# SCH_Solenoid_Door_Lock_using_EM-18_2023-.net
KiCad netlist of a schematic drawn in EasyEDA
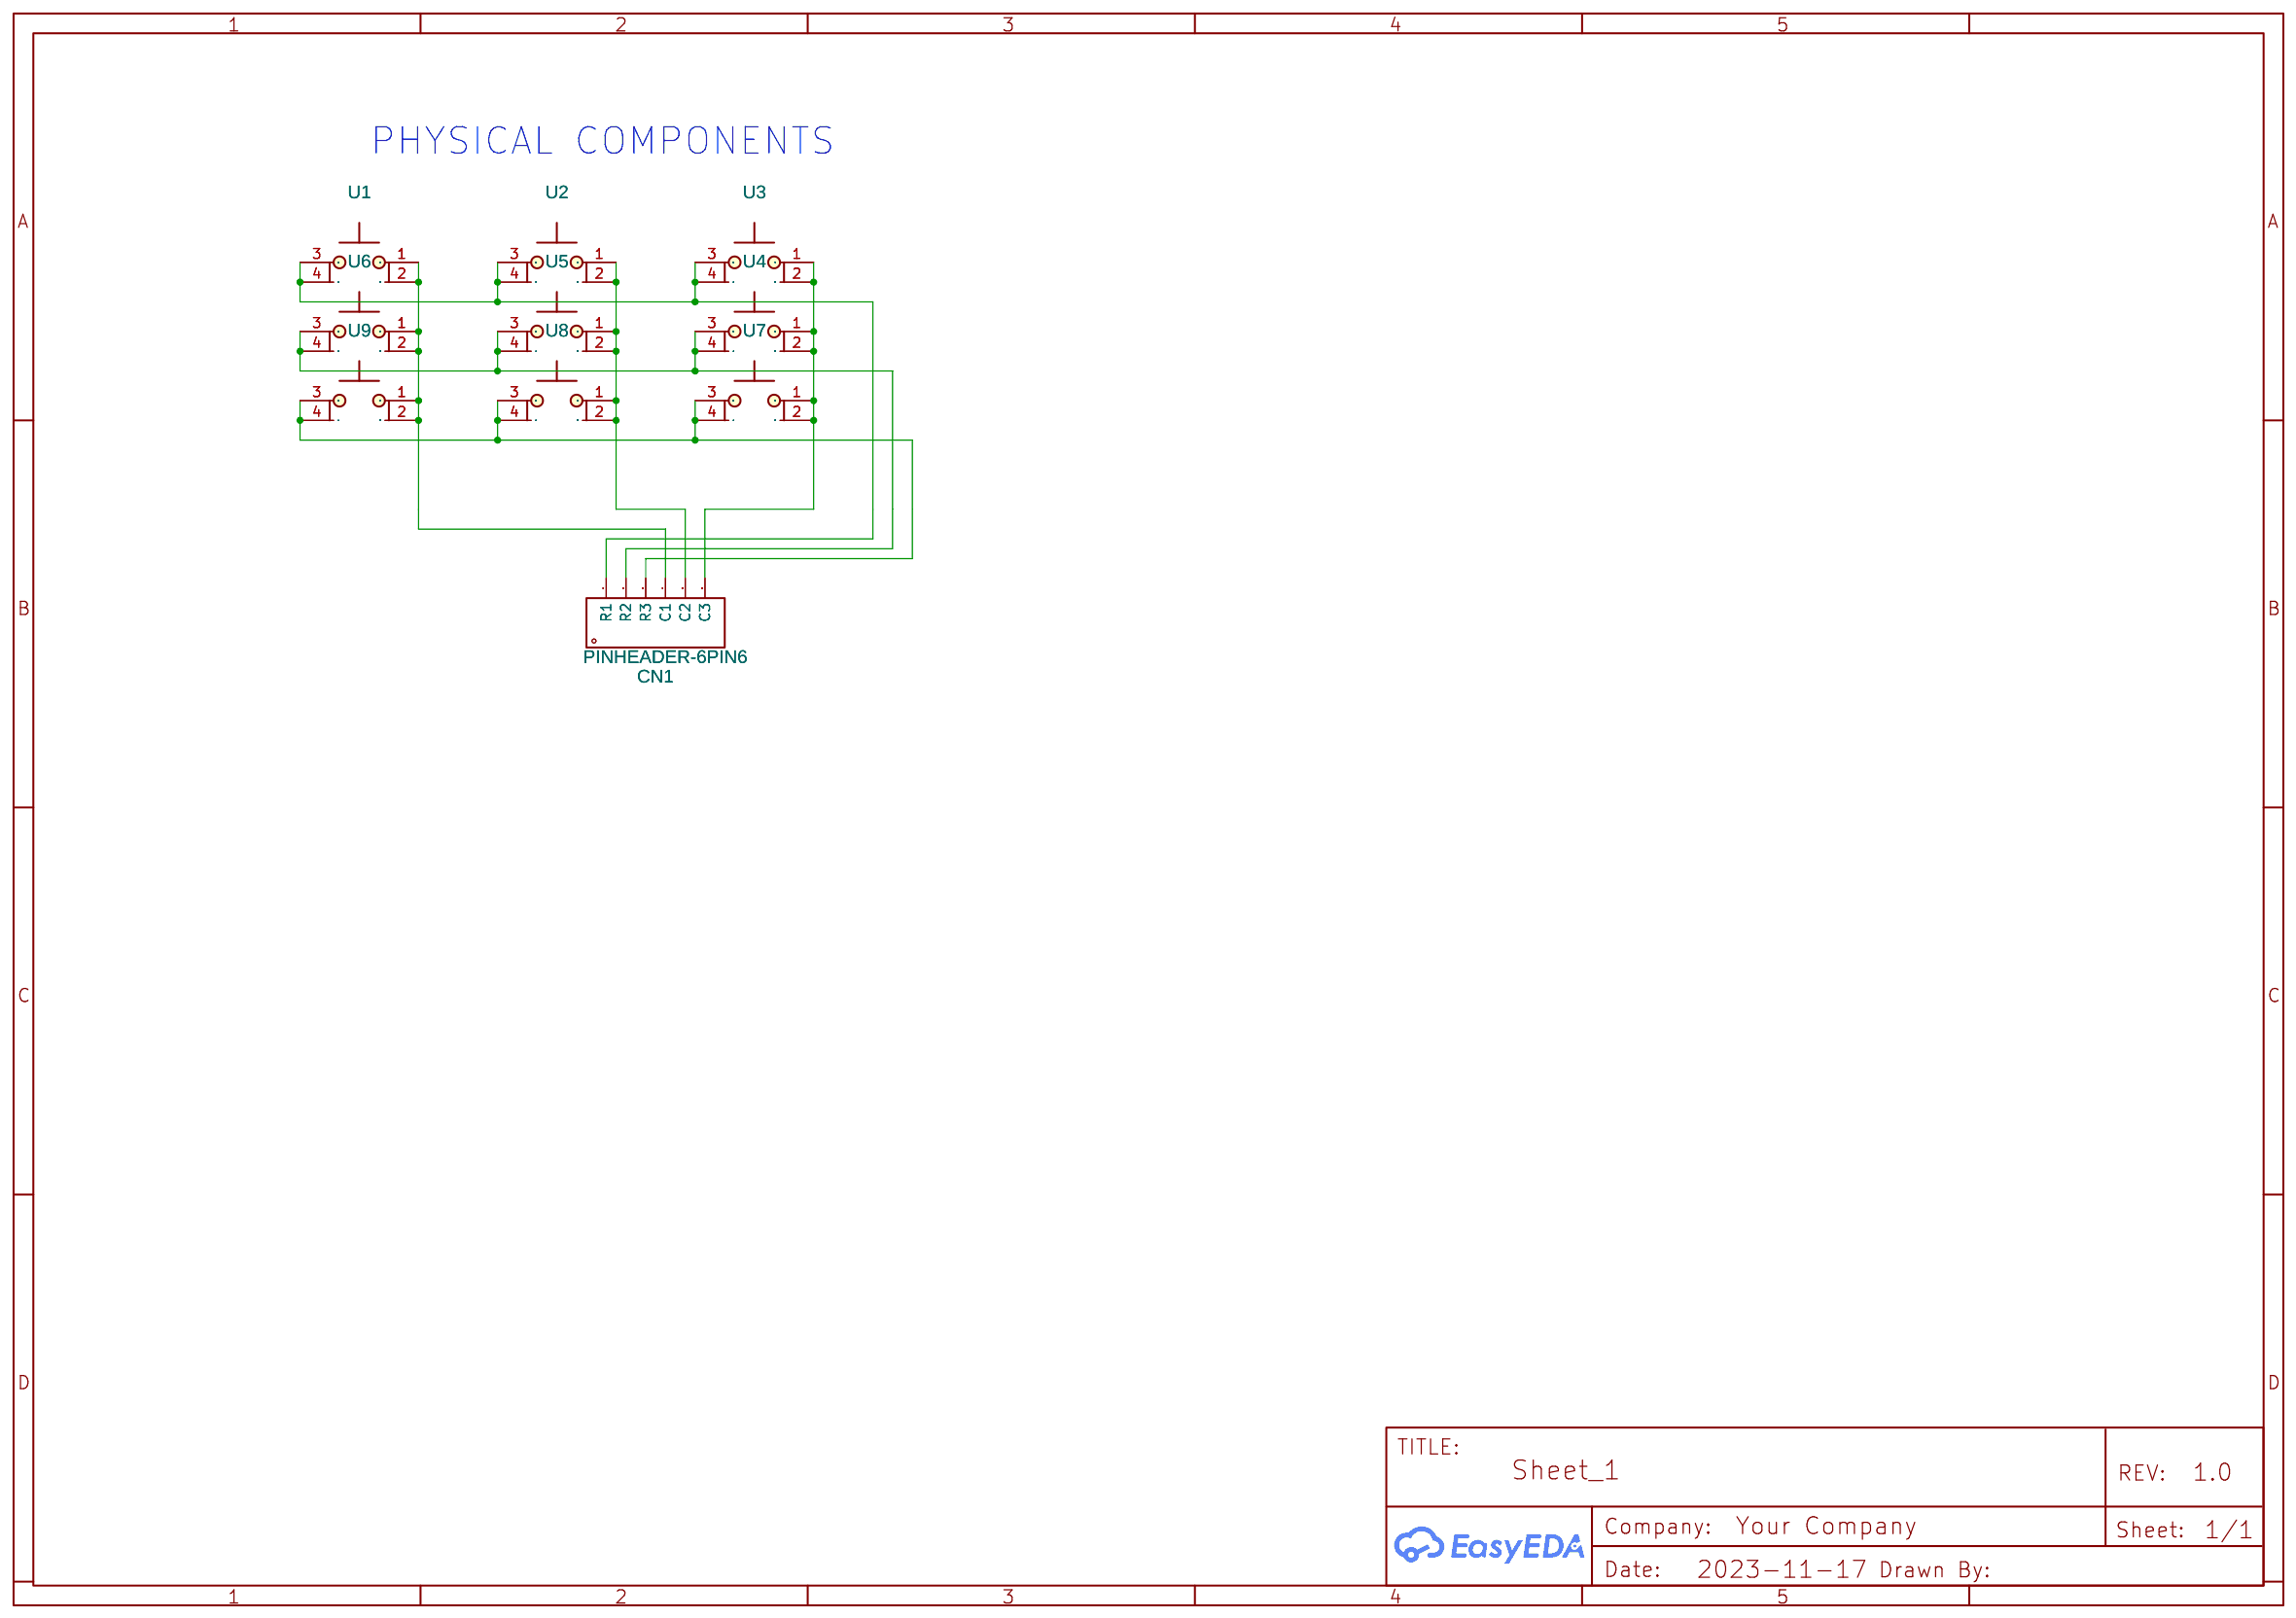
[diagram p0: 3x3 KeyPad]
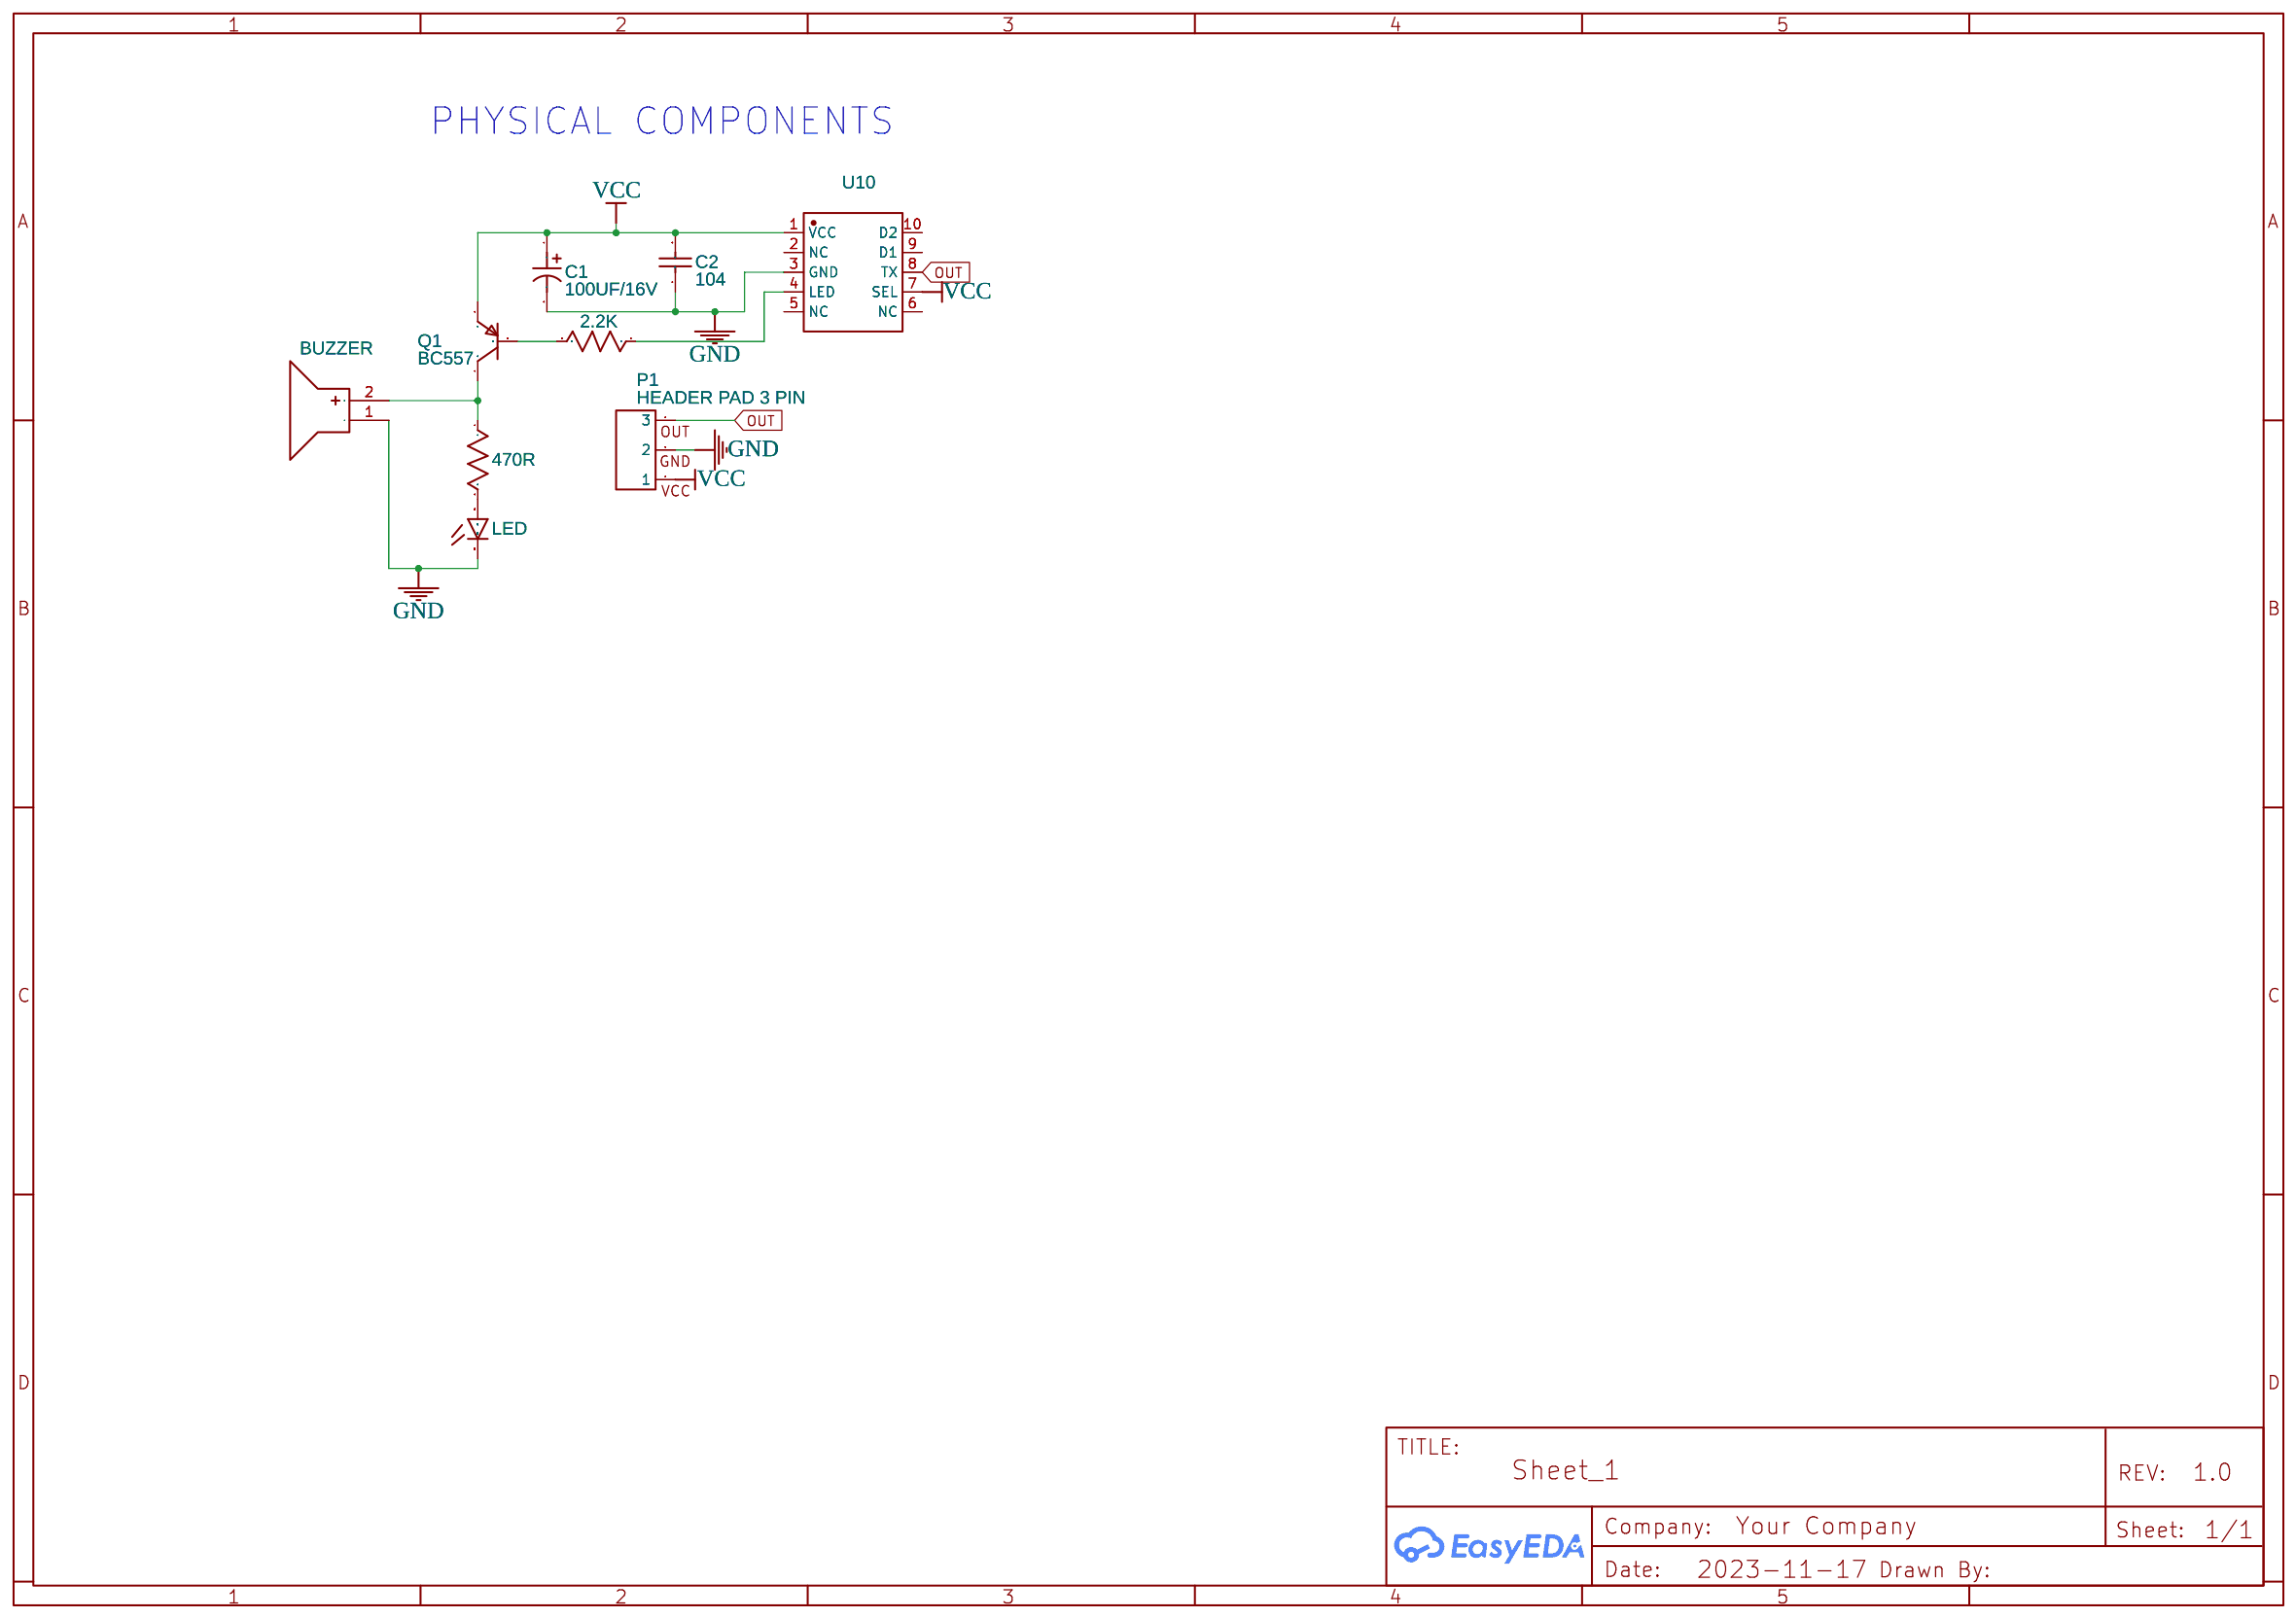
[diagram p1: EM-18 Module]
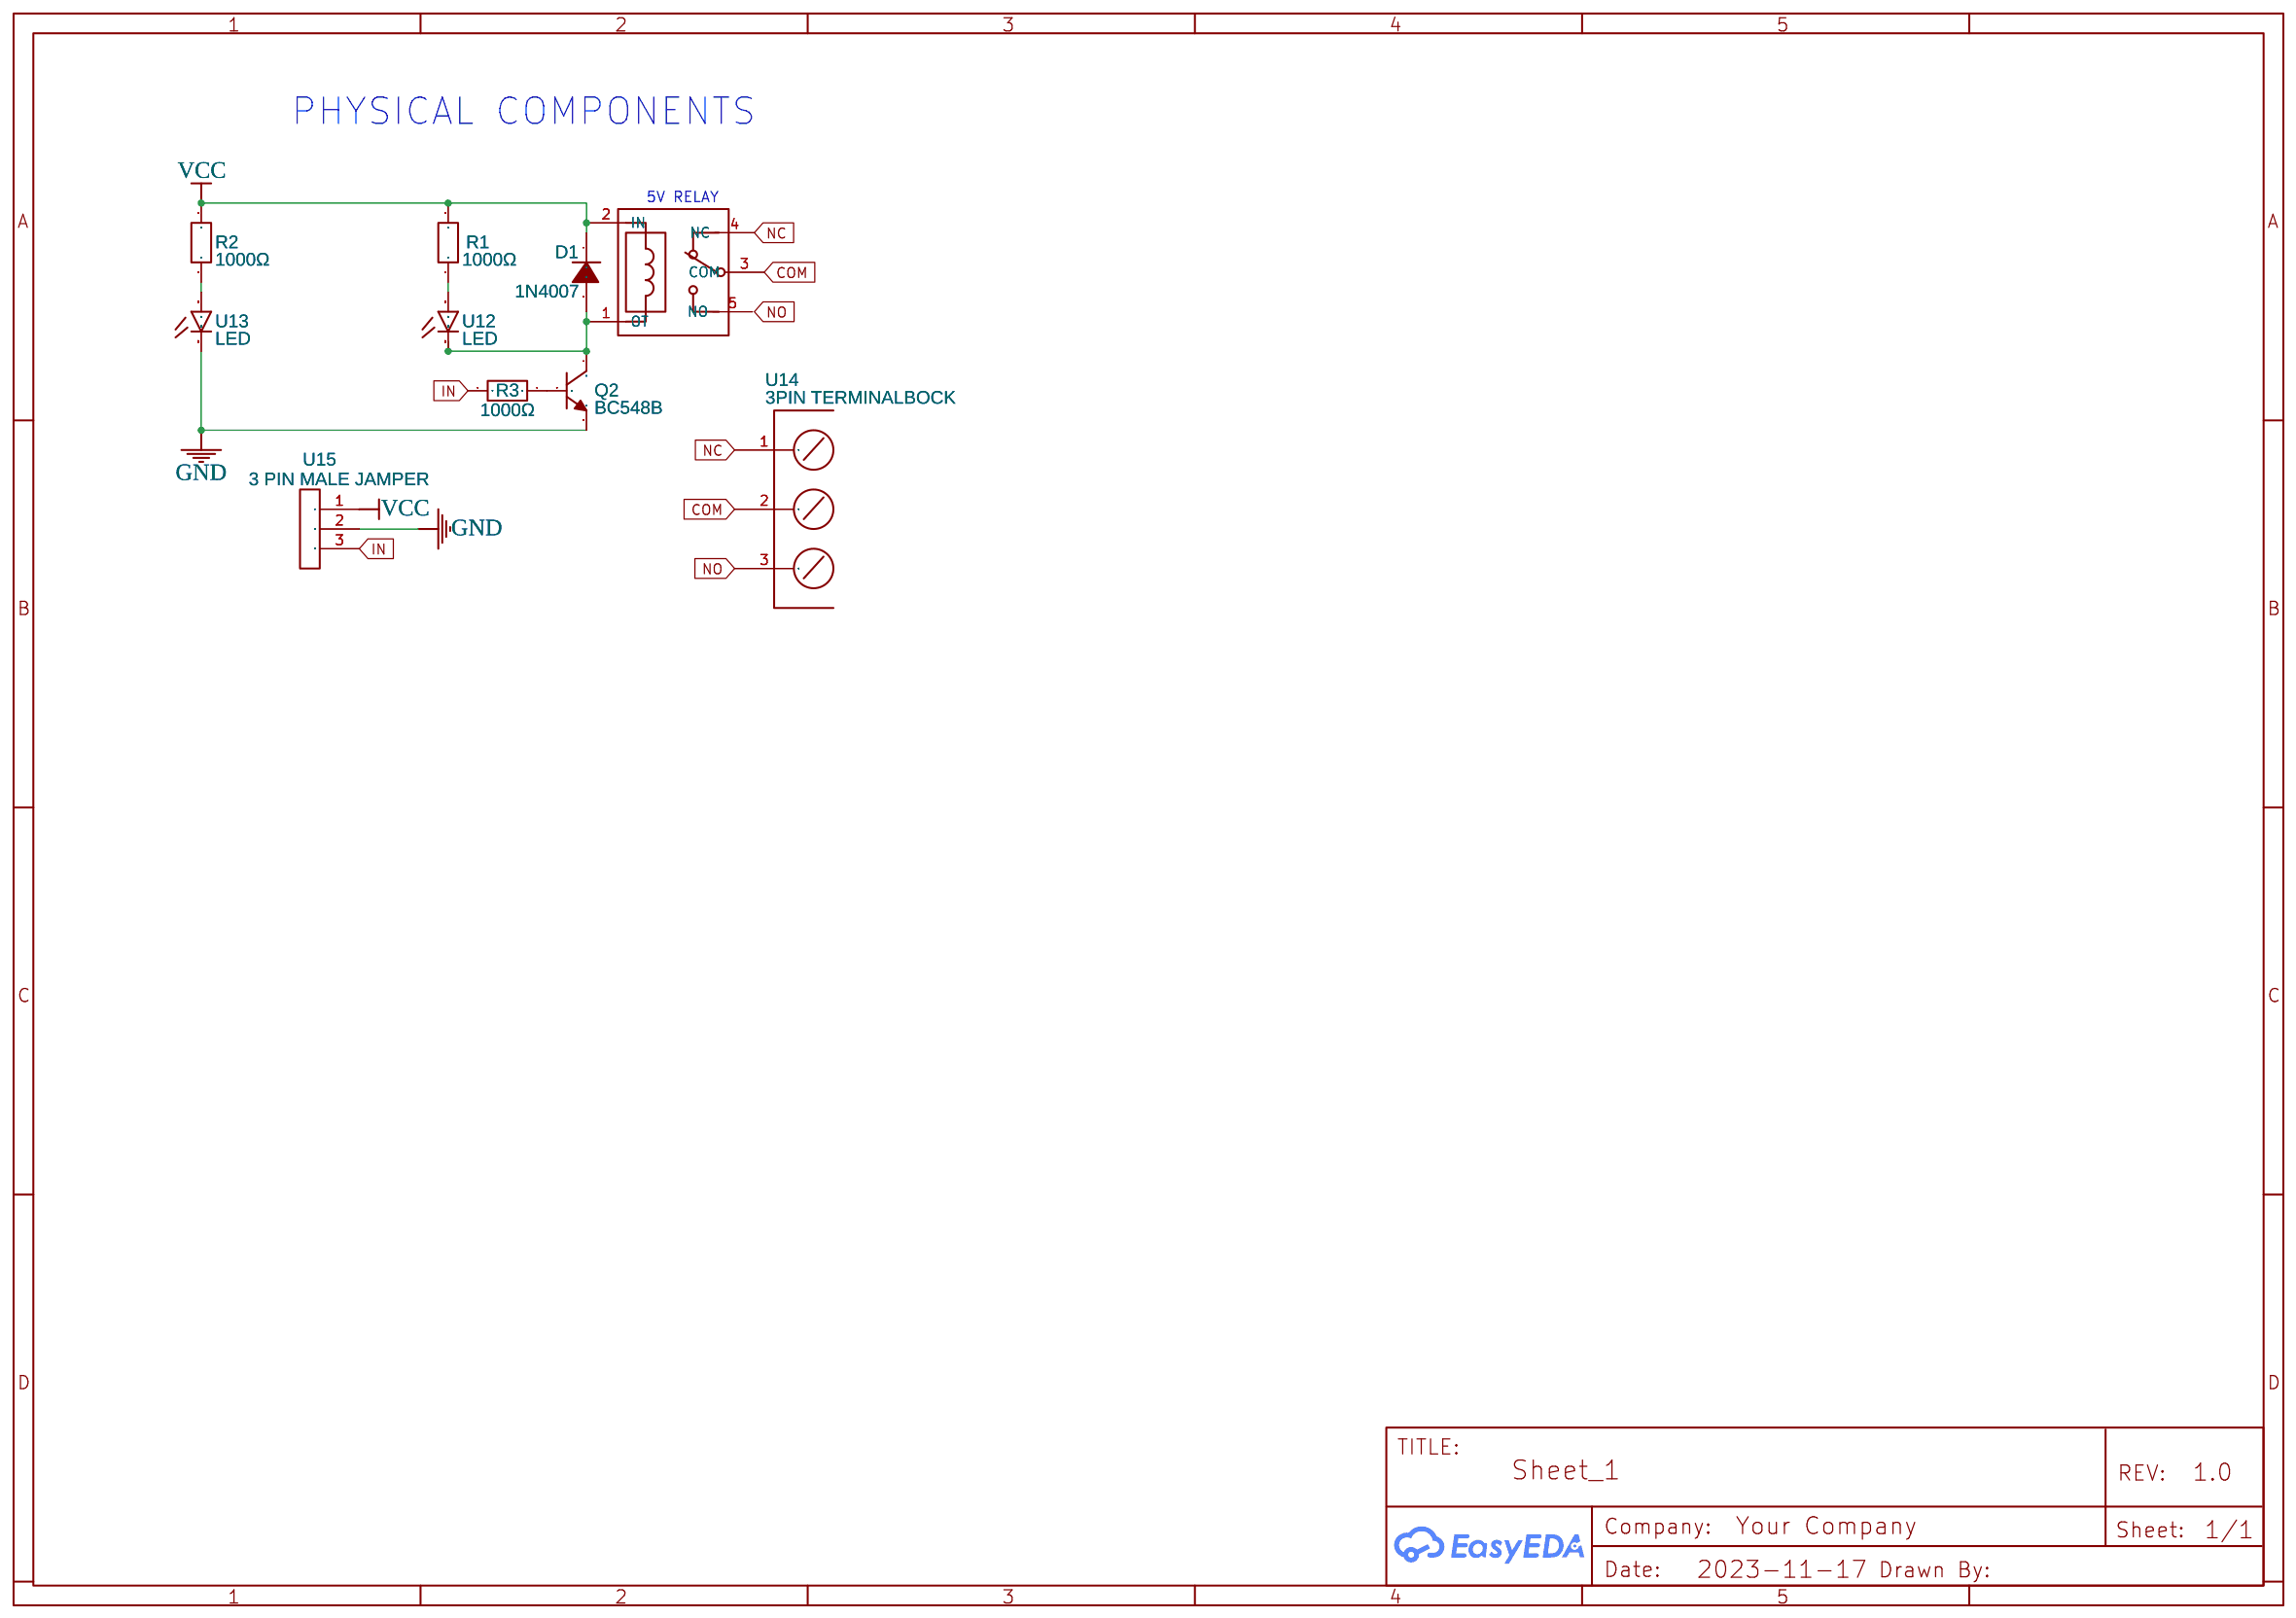
[diagram p2: Relay Module]
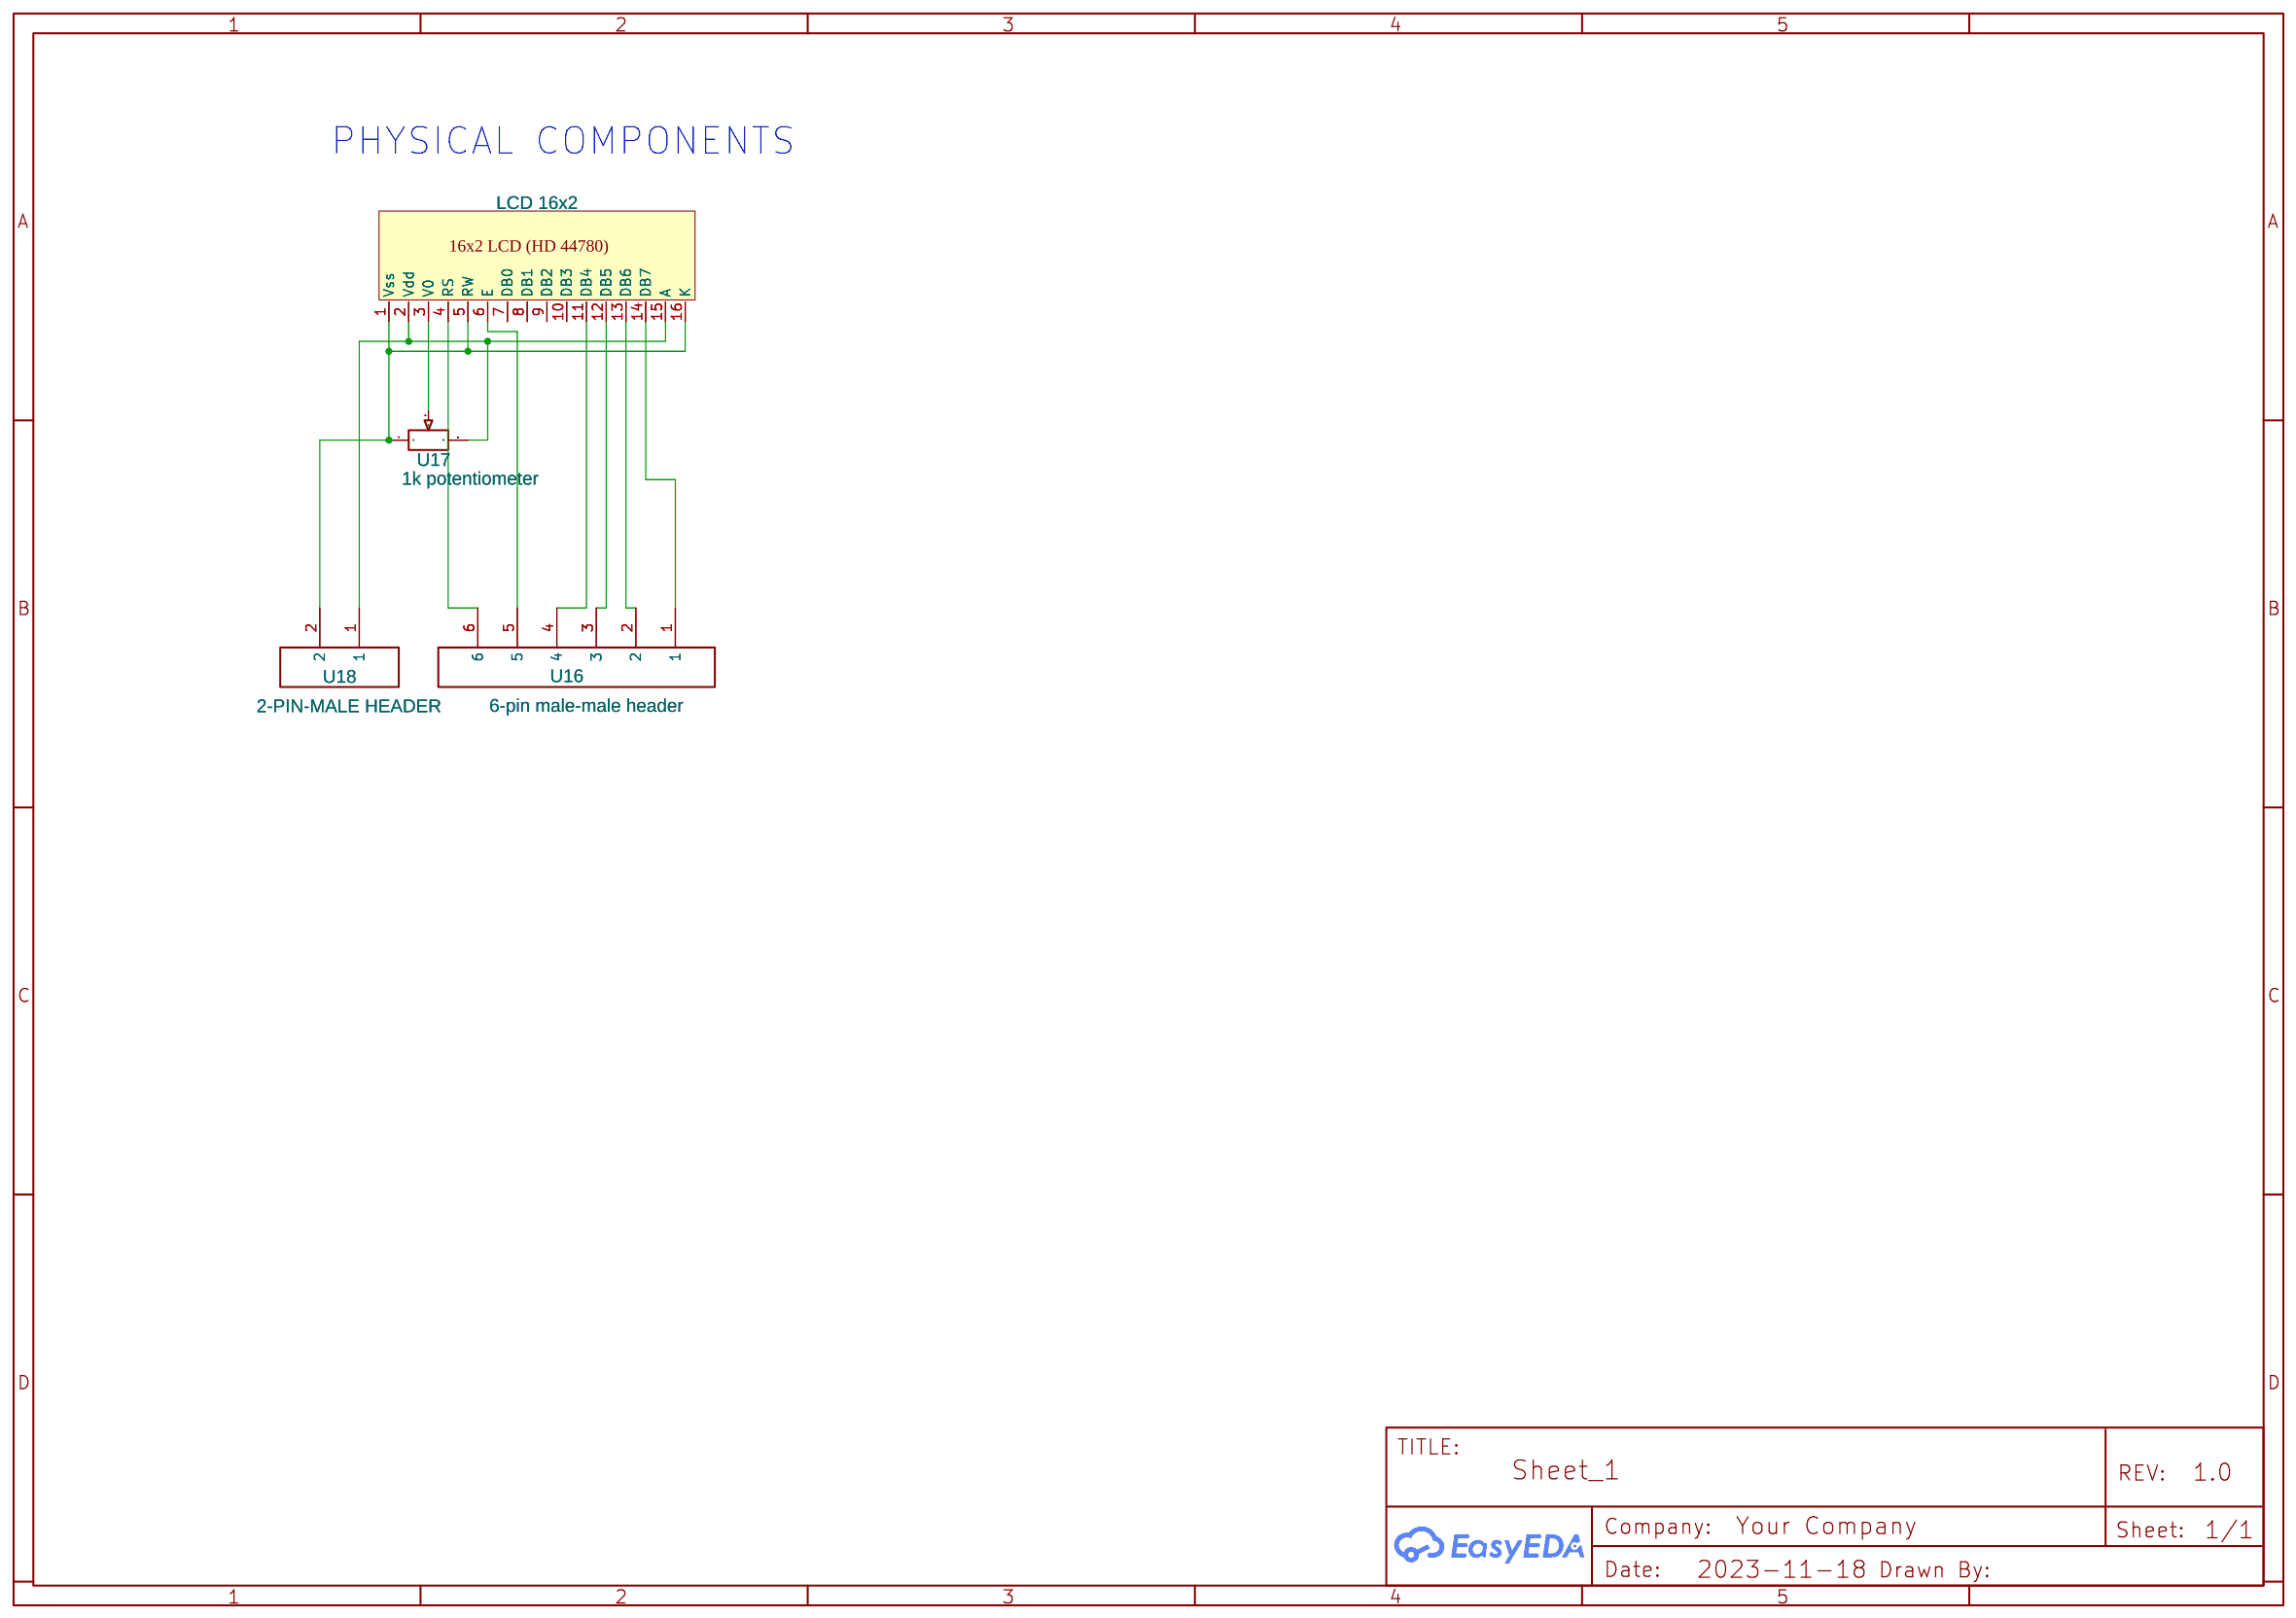
[diagram p3: LCD Display]
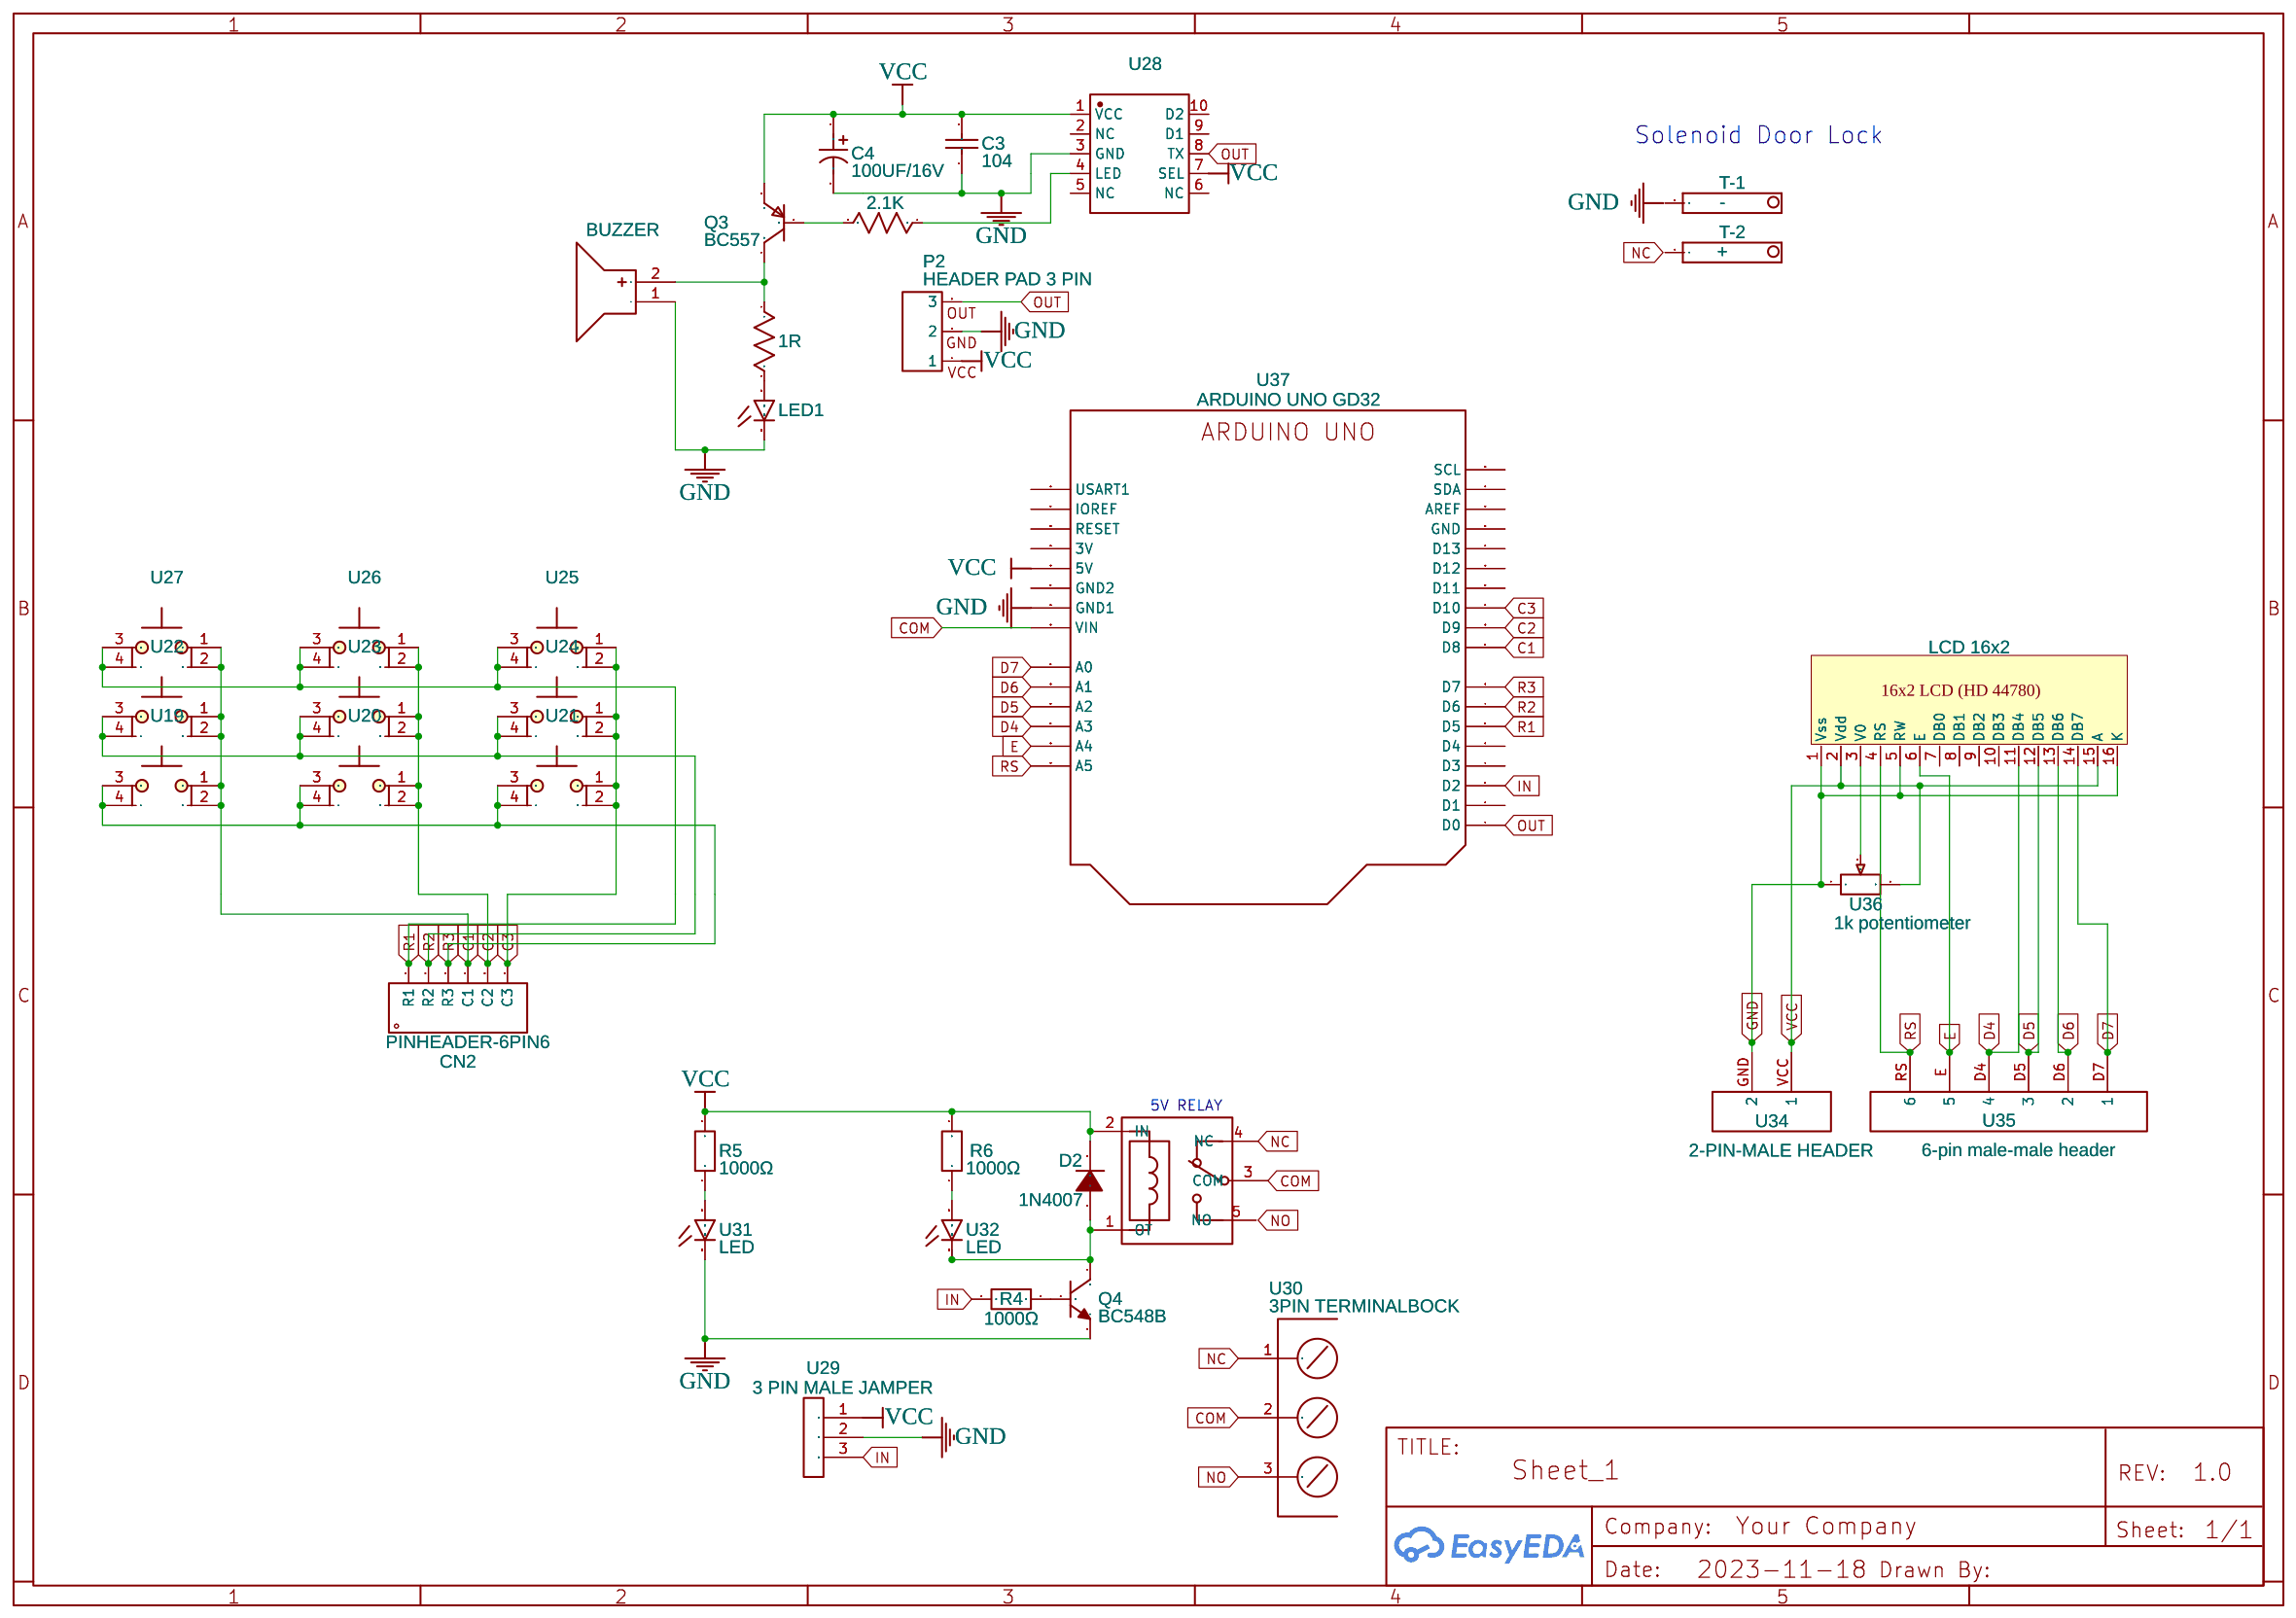
[diagram p4: Final Display]
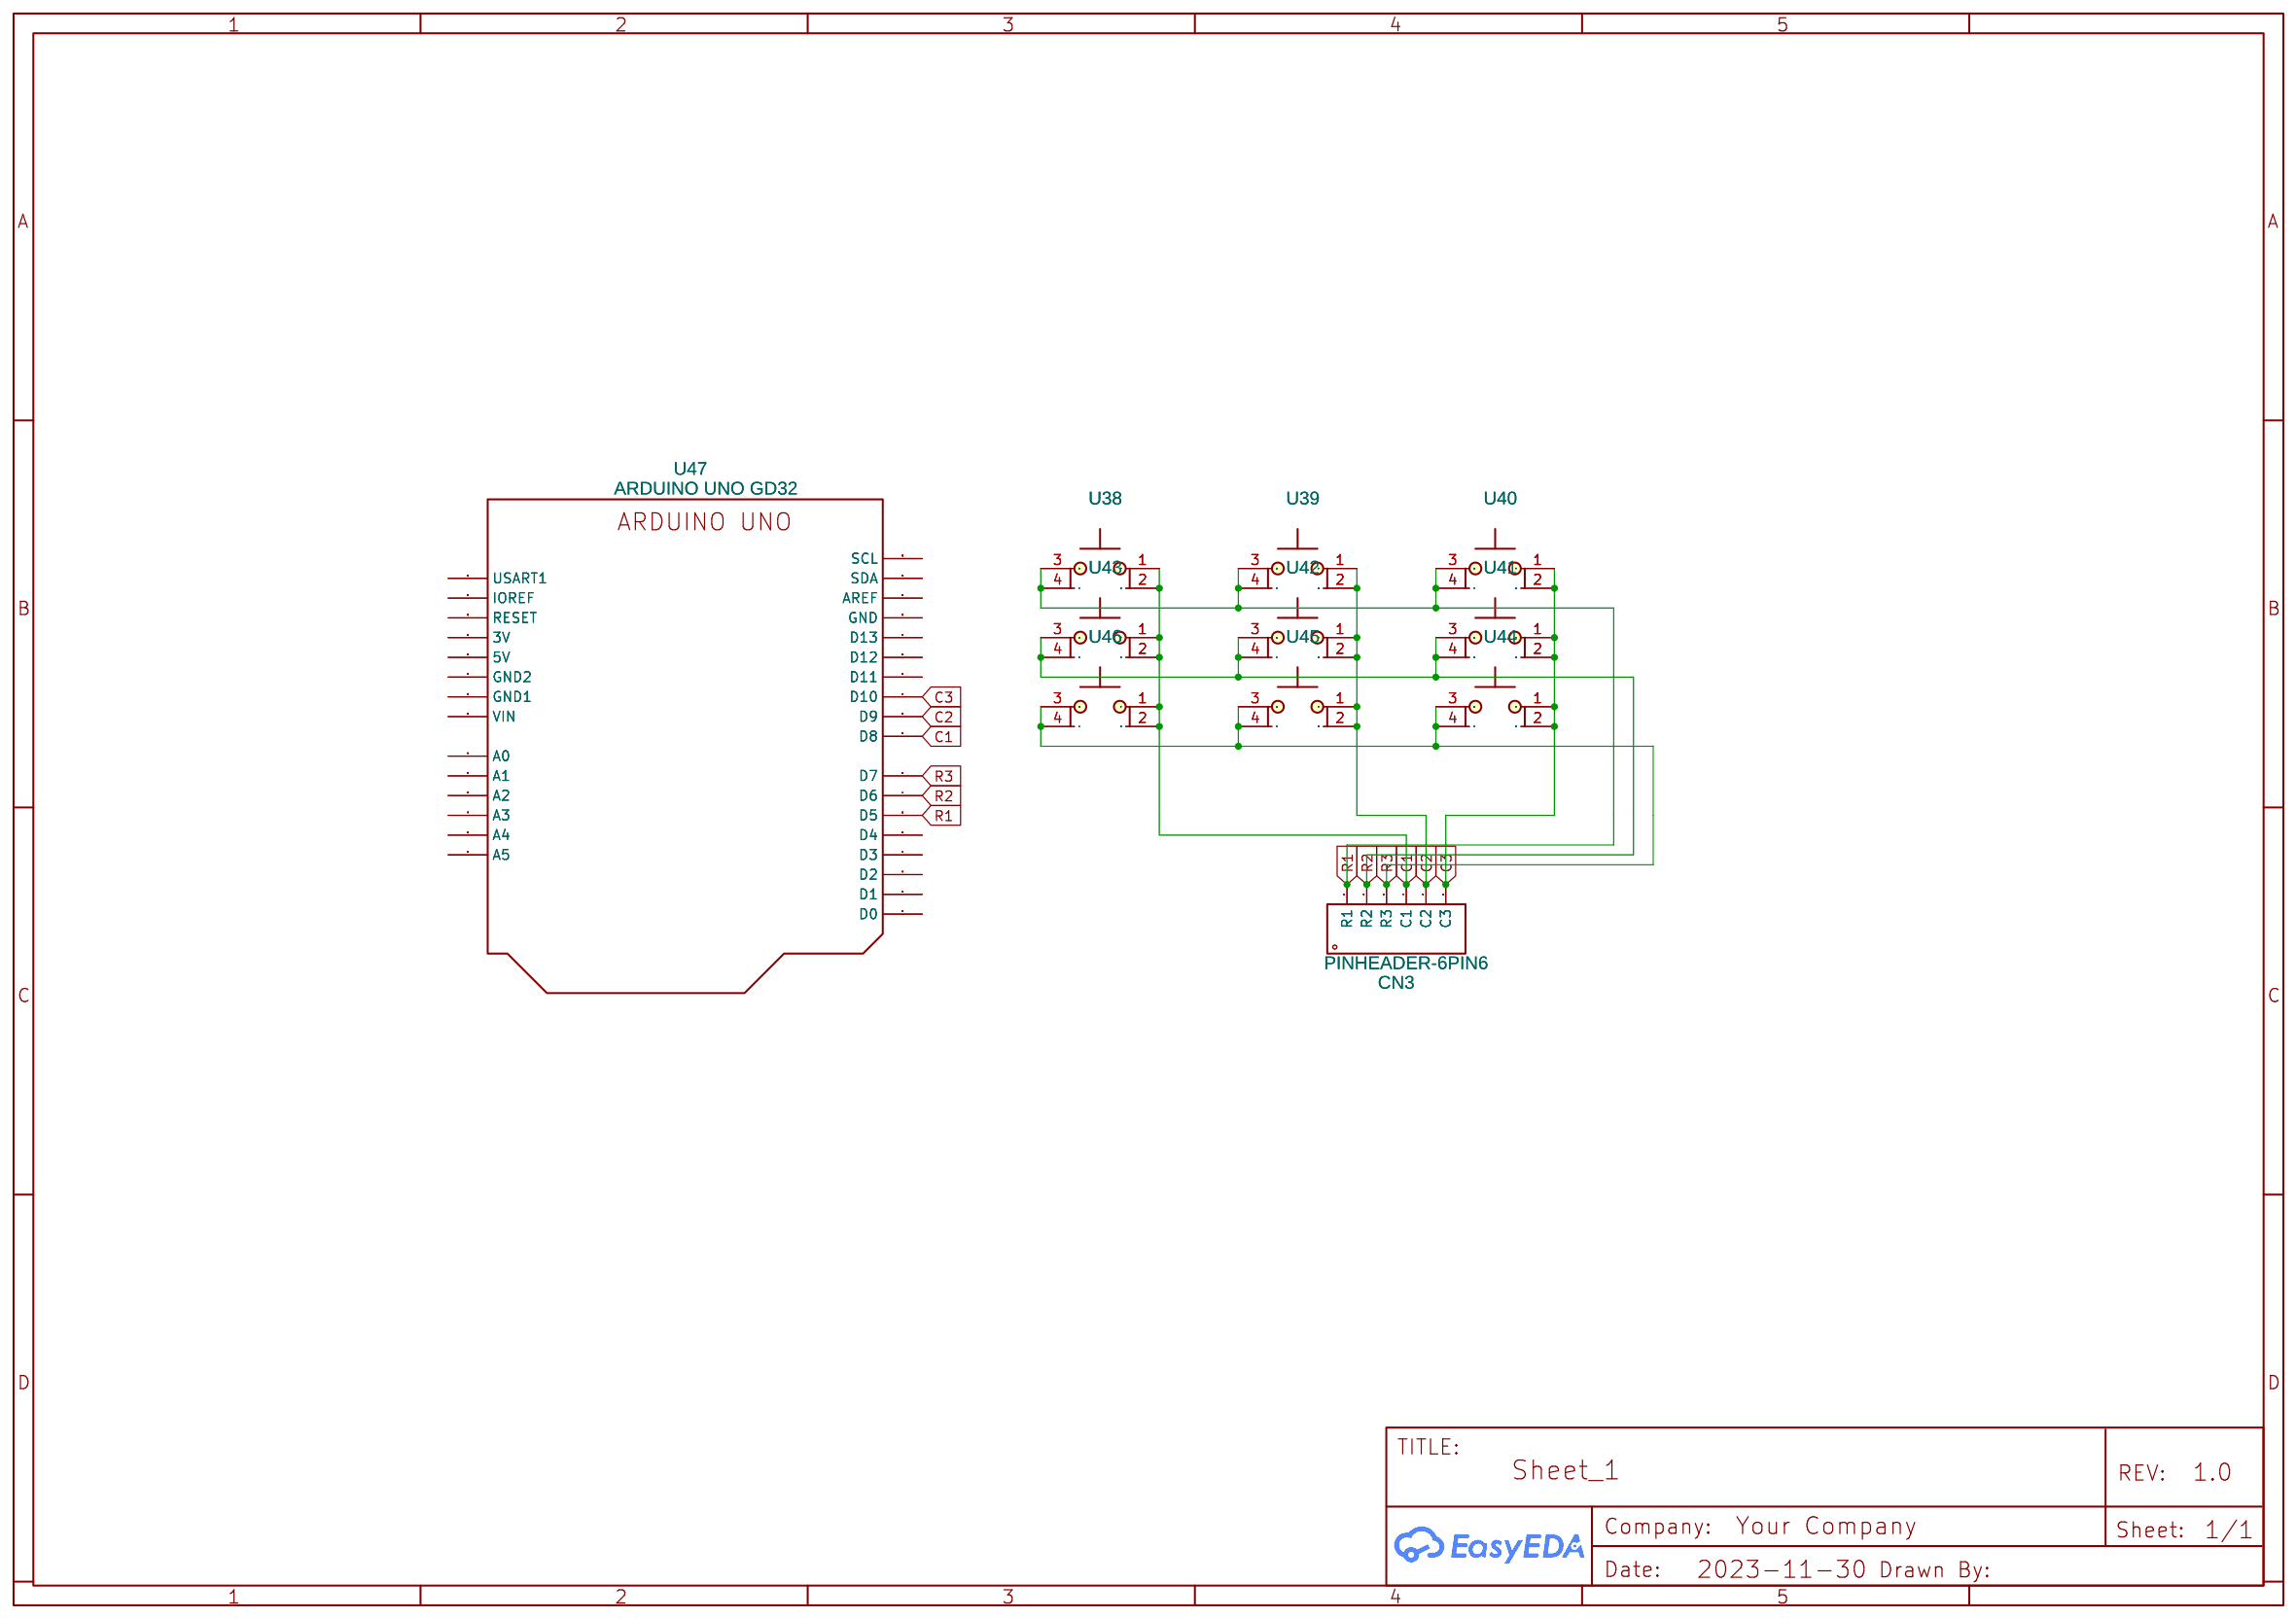
[diagram p5: Arduino_Keypad]
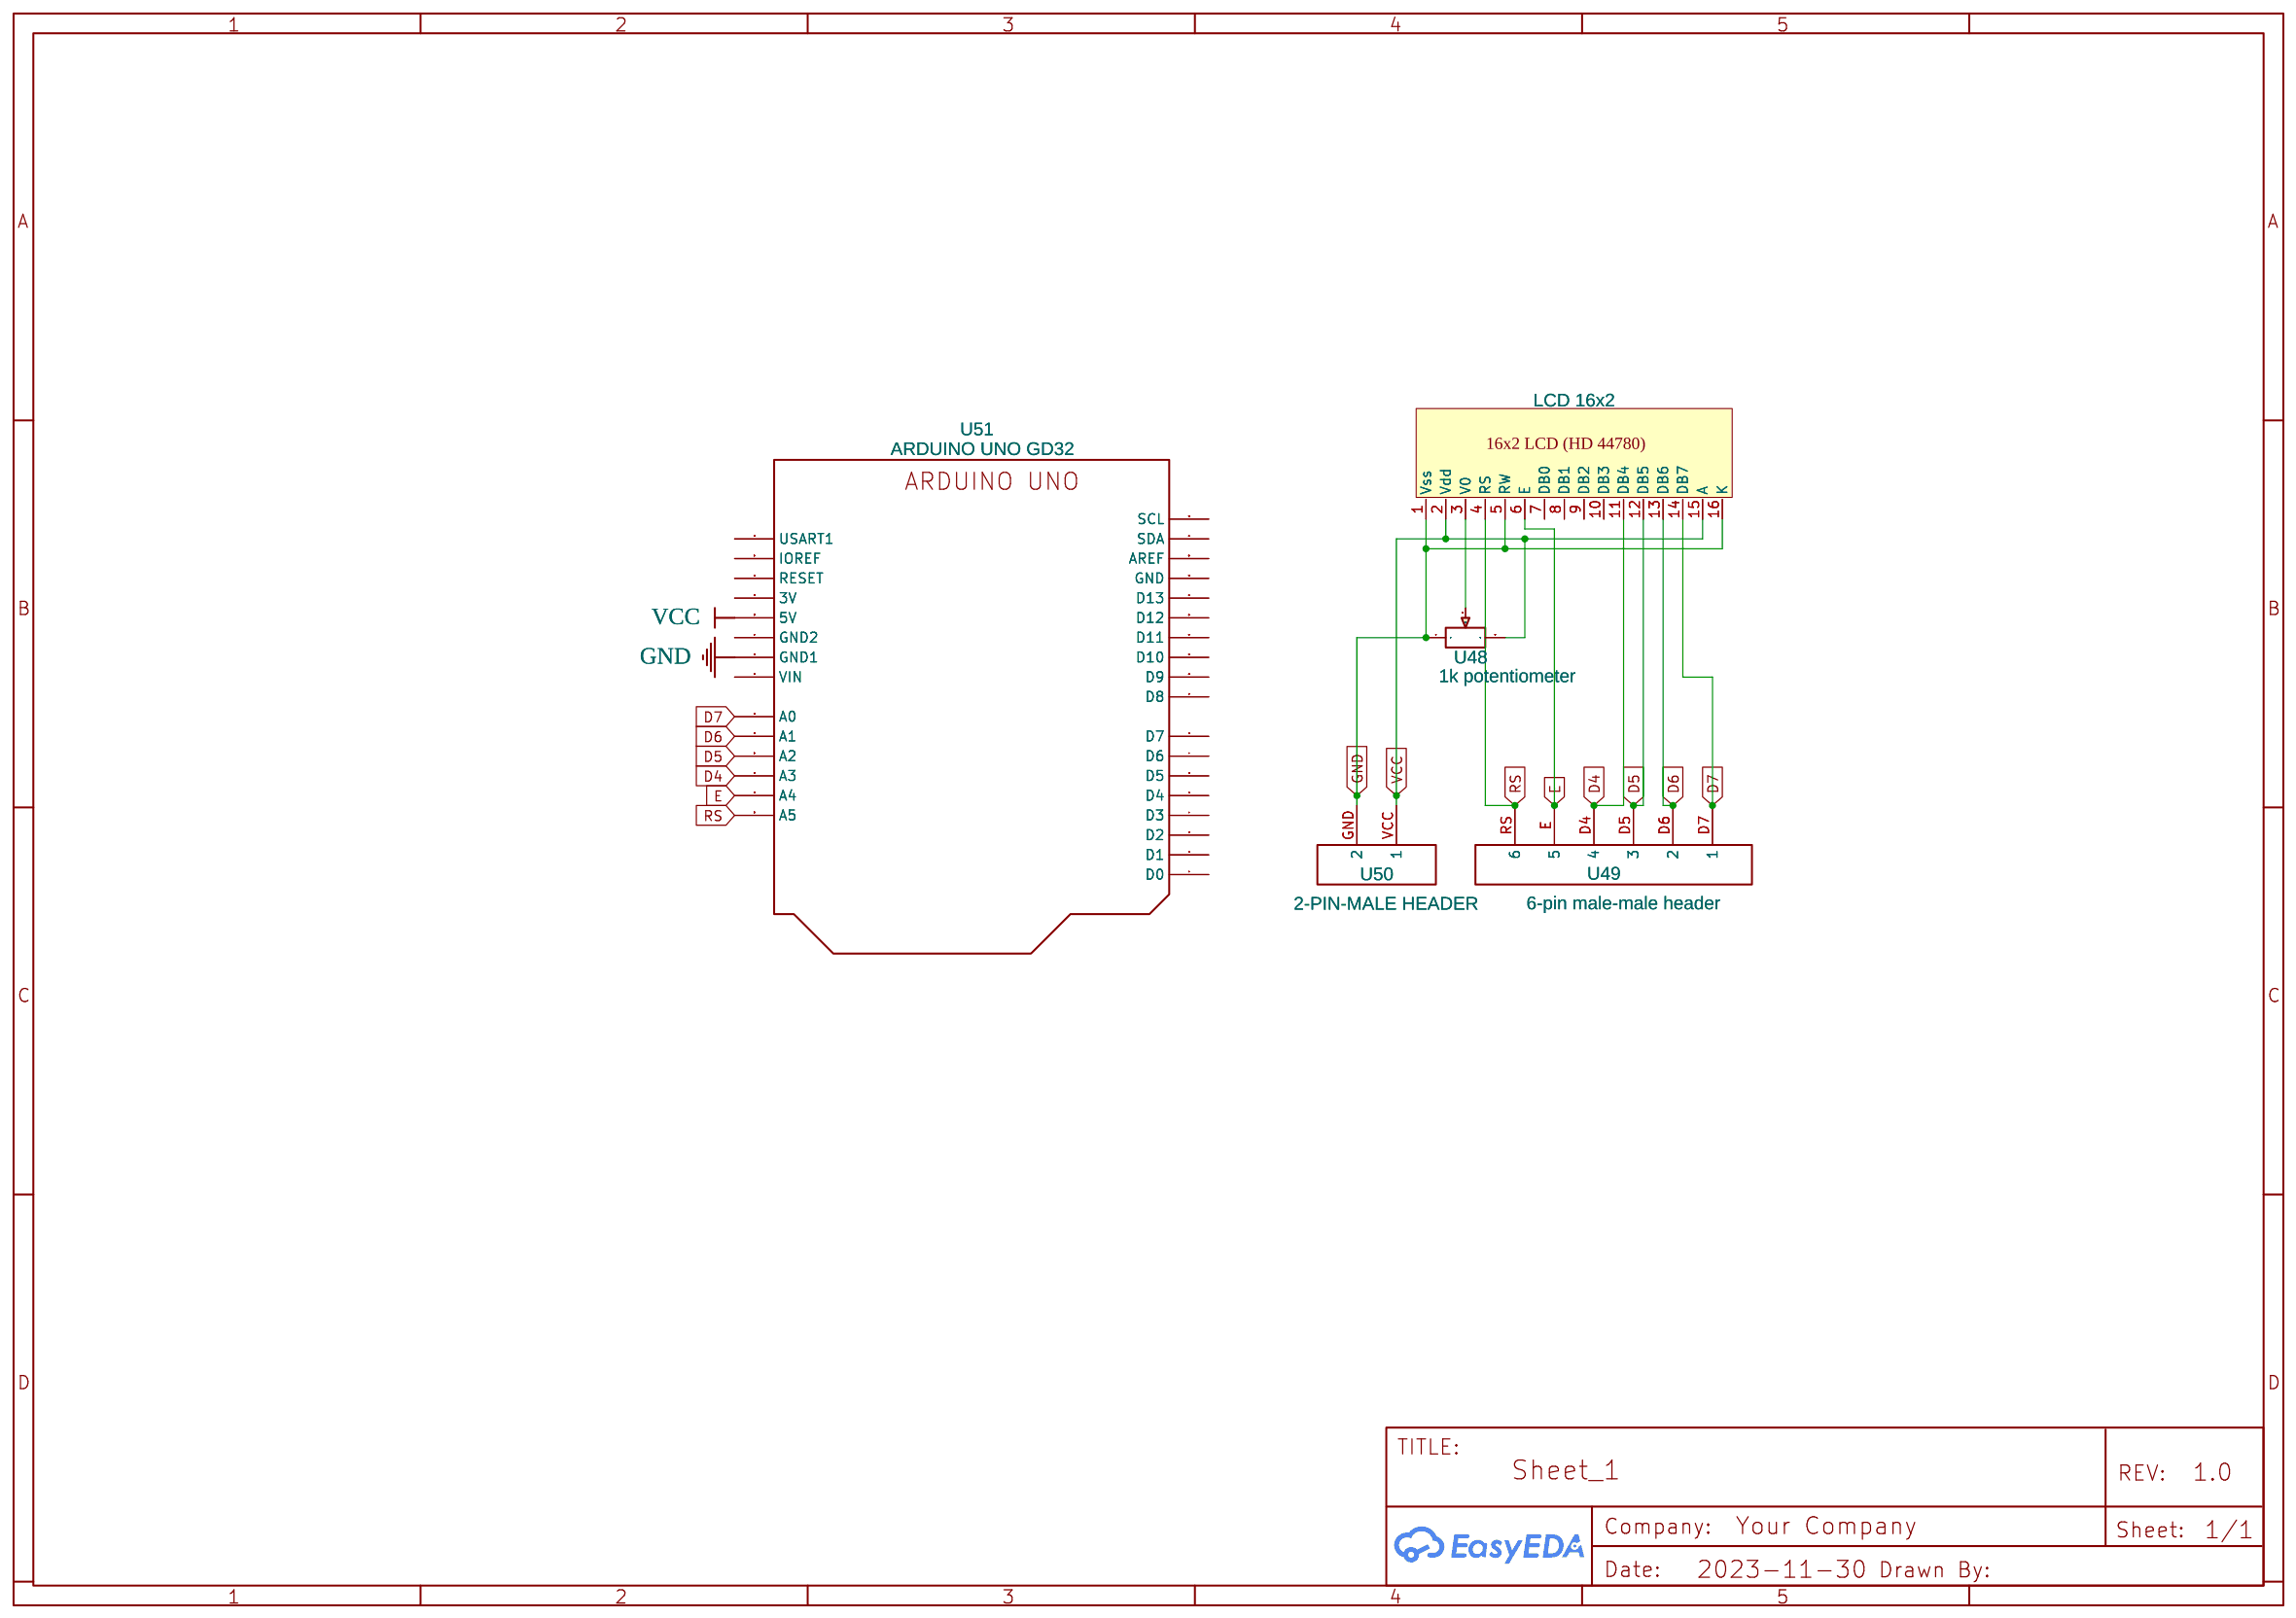
[diagram p6: Arduino_LCD]
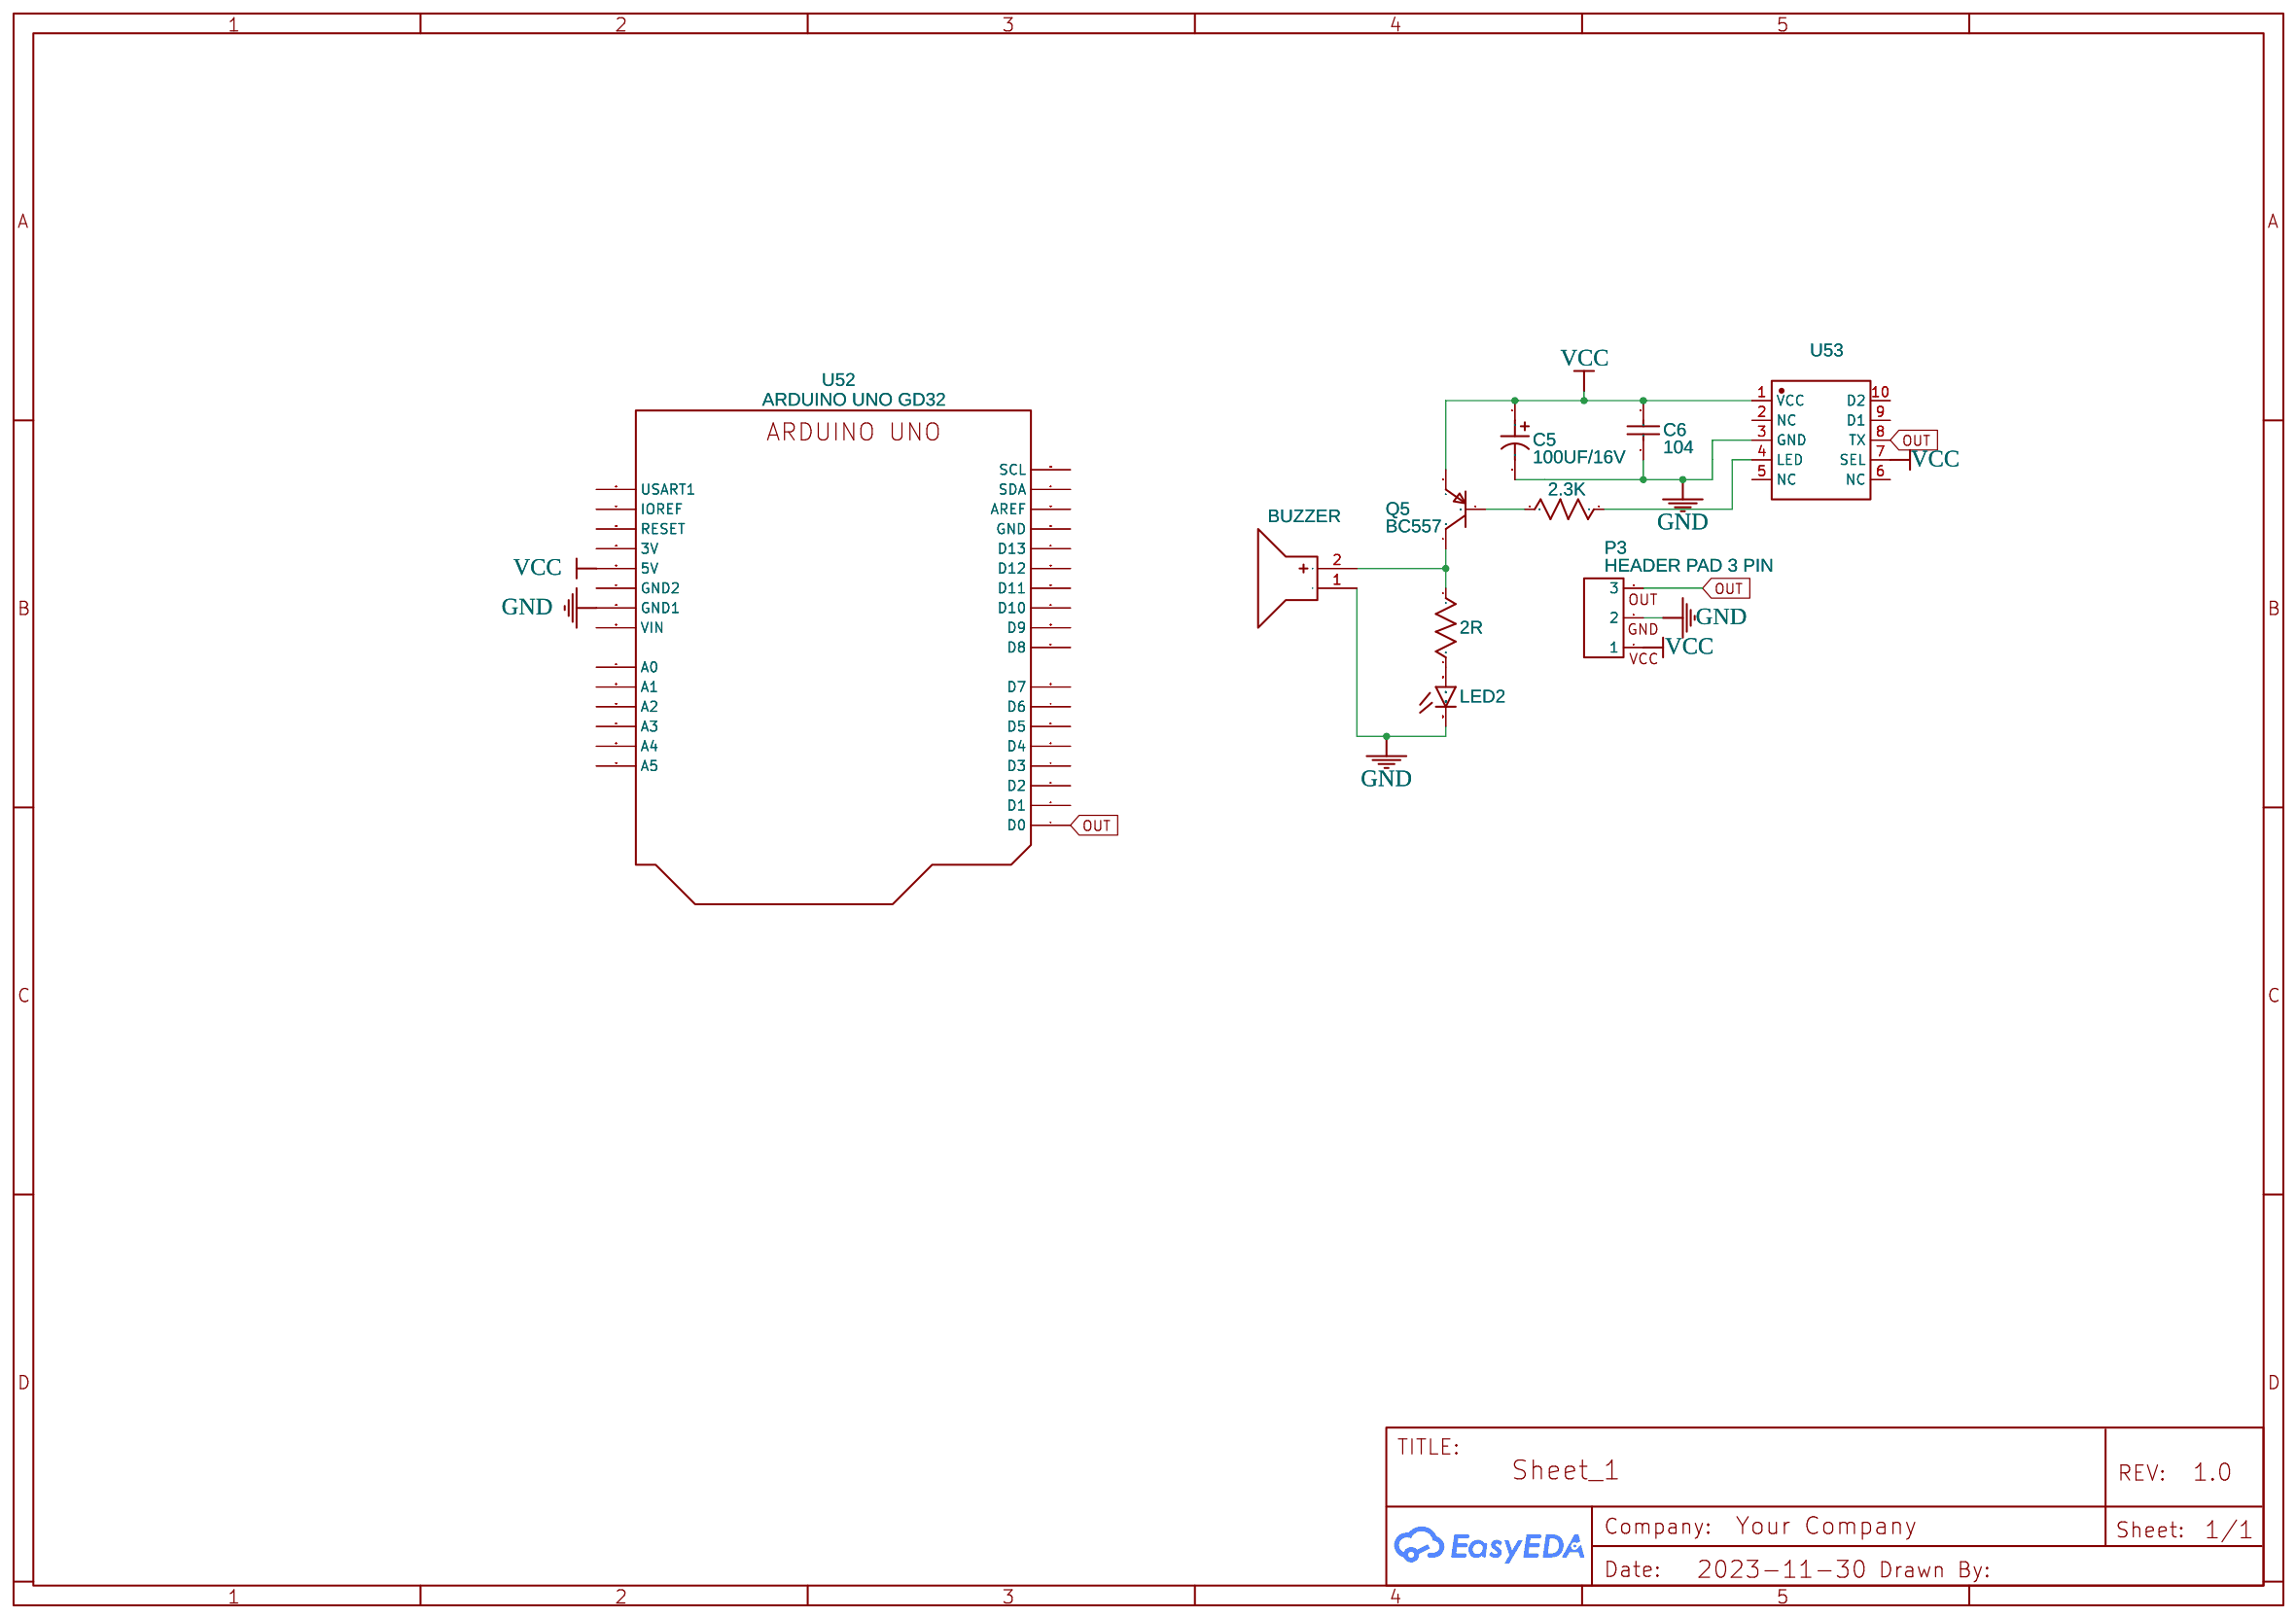
[diagram p7: Arduino_EM-18 Module]
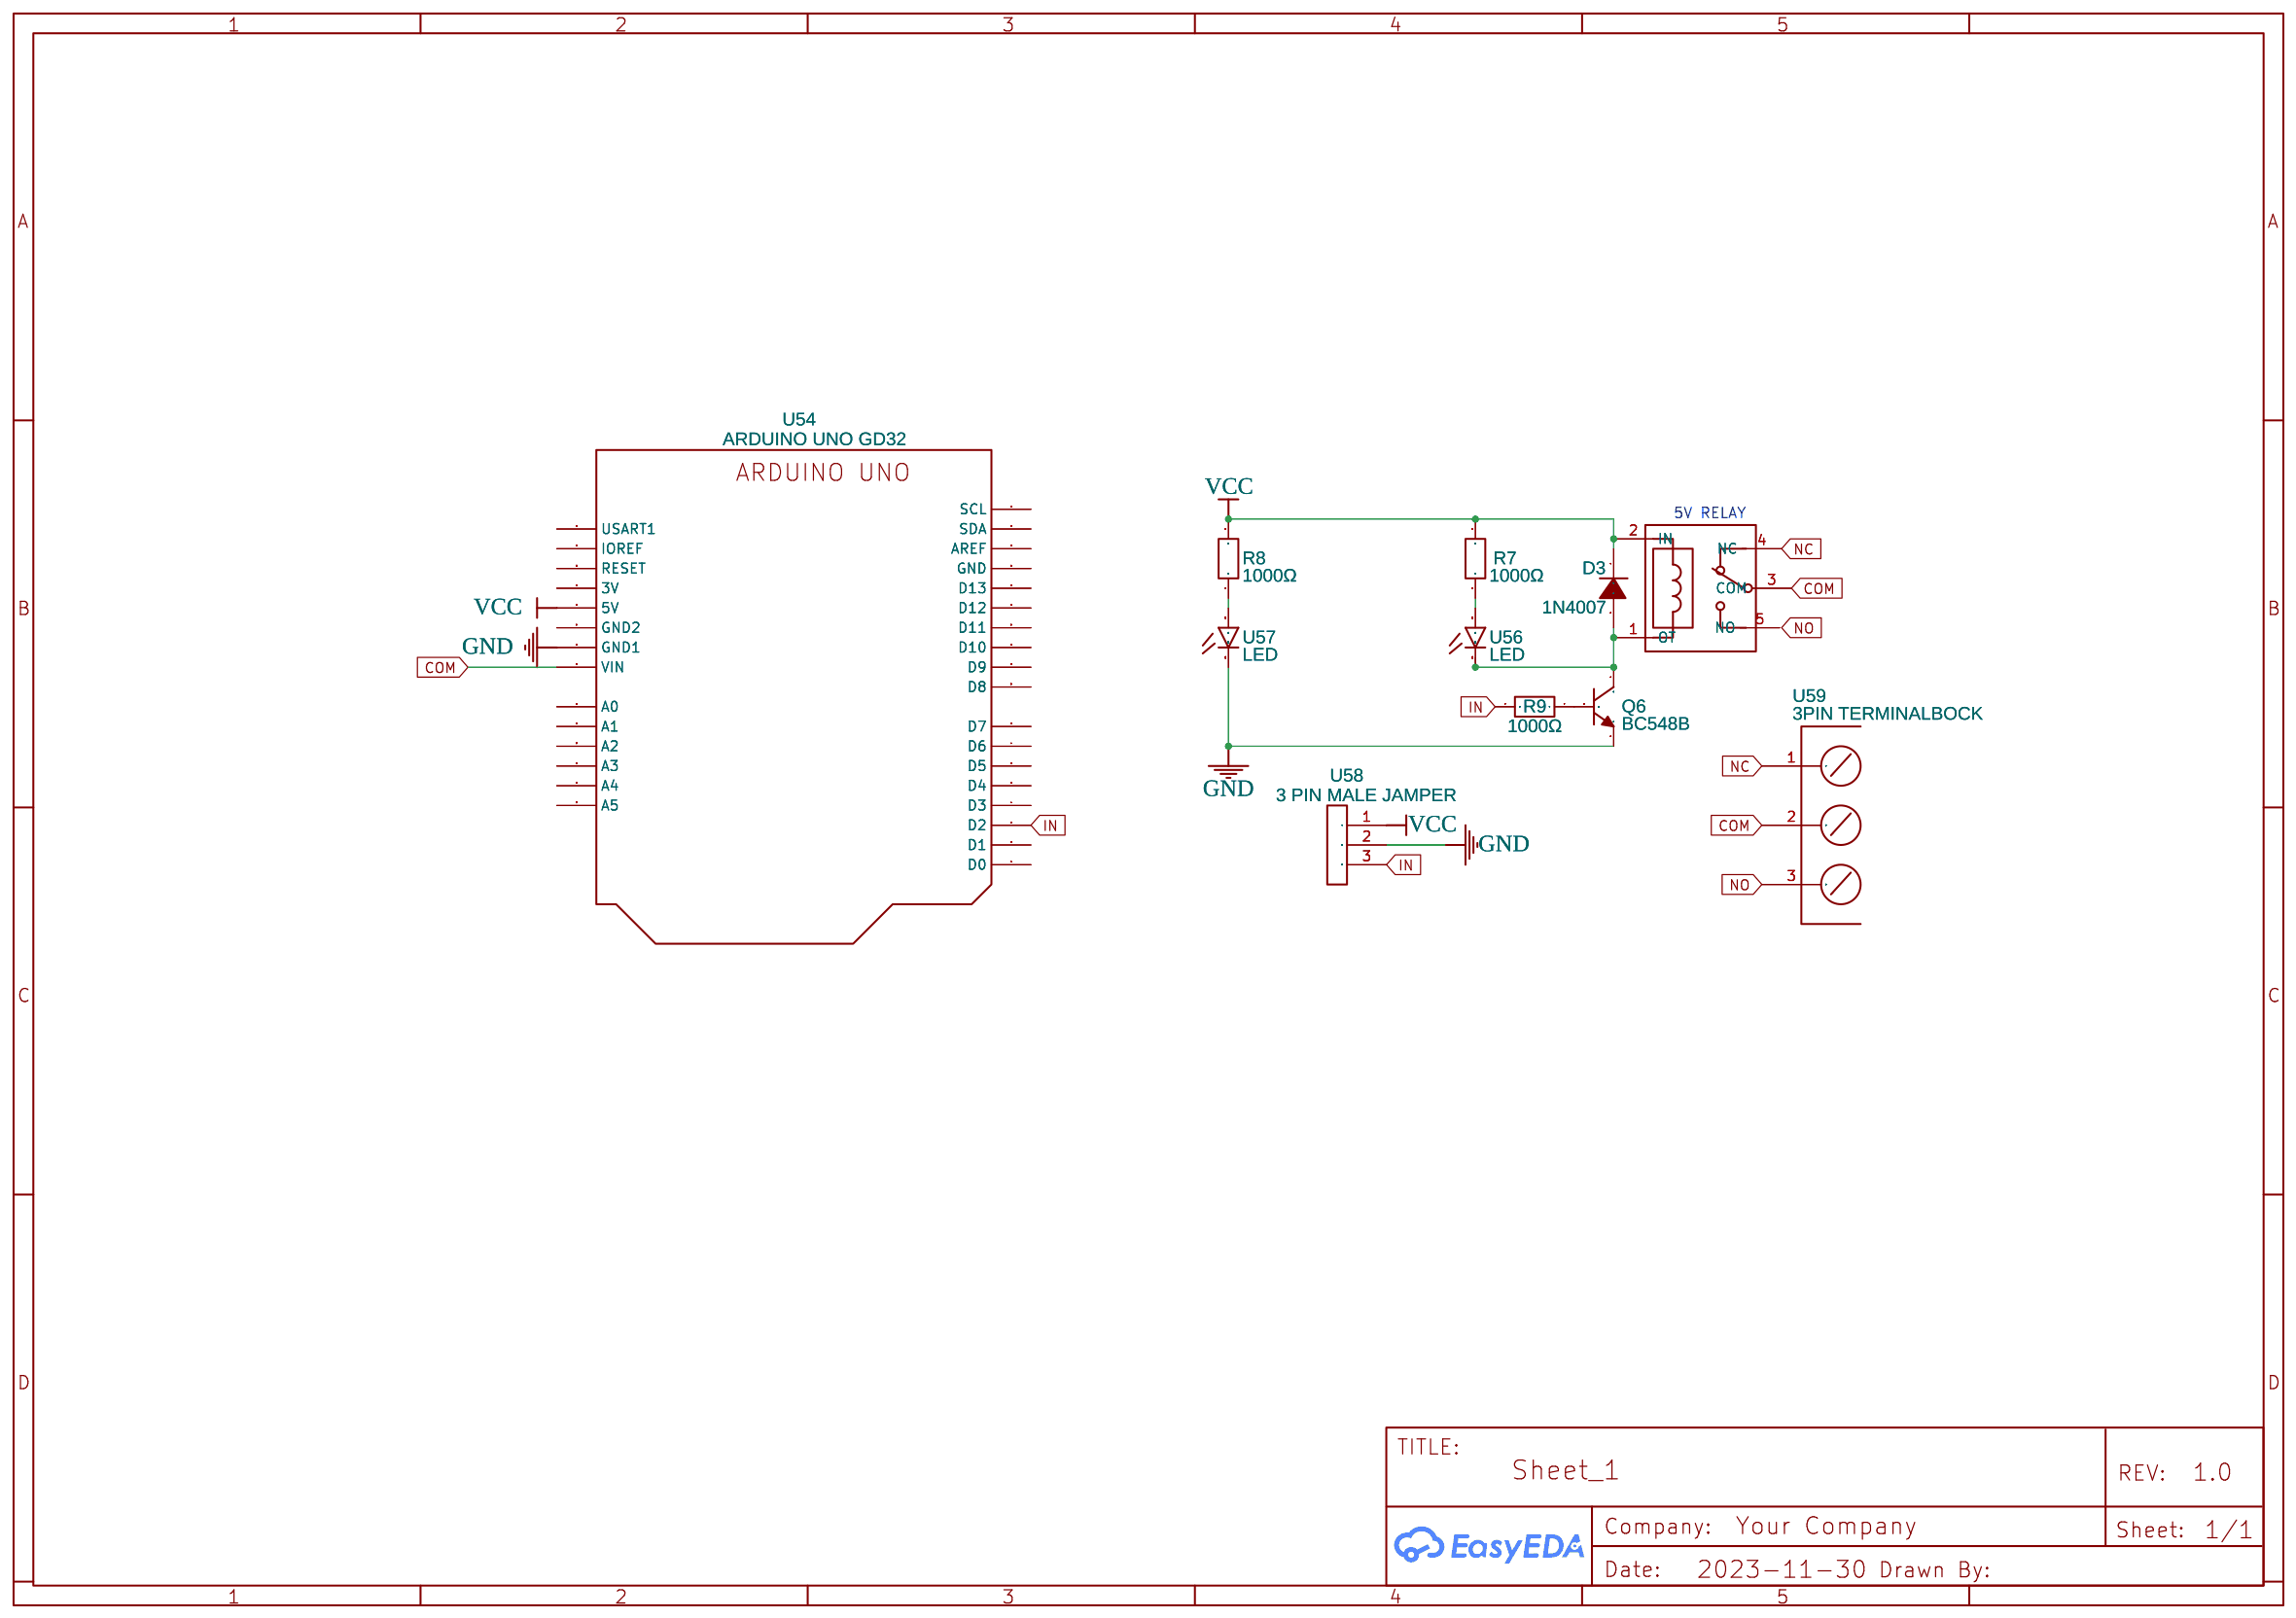
[diagram p8: Arduino_Relay Module]

(export (version "E")
  (design (tool "Eeschema 10.0.6"))
  (components
    (comp (ref "CN1") (value "PINHEADER-6PIN6") (libsource (lib "") (part "PINHEADER-6PIN6")))
    (comp (ref "U1") (value "NO") (libsource (lib "") (part "ESO_SPST_Momentary")))
    (comp (ref "U2") (value "NO") (libsource (lib "") (part "ESO_SPST_Momentary")))
    (comp (ref "U3") (value "NO") (libsource (lib "") (part "ESO_SPST_Momentary")))
    (comp (ref "U4") (value "NO") (libsource (lib "") (part "ESO_SPST_Momentary")))
    (comp (ref "U5") (value "NO") (libsource (lib "") (part "ESO_SPST_Momentary")))
    (comp (ref "U6") (value "NO") (libsource (lib "") (part "ESO_SPST_Momentary")))
    (comp (ref "U7") (value "NO") (libsource (lib "") (part "ESO_SPST_Momentary")))
    (comp (ref "U8") (value "NO") (libsource (lib "") (part "ESO_SPST_Momentary")))
    (comp (ref "U9") (value "NO") (libsource (lib "") (part "ESO_SPST_Momentary")))
    (comp (ref "2.2K")
      (value "~")
      (fields (field (name "Manufacturer") "Huaxing Mechanical-Elec."))
      (libsource (lib "") (part "1/4W-2.2KΩ±1%"))
    )
    (comp (ref "470R")
      (value "~")
      (fields (field (name "Manufacturer") "Huaxing Mechanical-Elec."))
      (libsource (lib "") (part "1/4W-2.2KΩ±1%_1"))
    )
    (comp (ref "BUZZER1")
      (value "BUZZER")
      (fields (field (name "Manufacturer Part") "buzzer"))
      (libsource (lib "") (part "BUZZER"))
    )
    (comp (ref "C1")
      (value "100UF/16V")
      (fields (field (name "Manufacturer Part") "100uF/16V"))
      (libsource (lib "") (part "100UF/16V"))
    )
    (comp (ref "C2")
      (value "104")
      (fields
        (field (name "Manufacturer Part") "Suppression Capacitor222M/250V")
        (field (name "Manufacturer") "ReliaPro")
      )
      (libsource (lib "") (part "104nf"))
    )
    (comp (ref "LED") (value "~") (libsource (lib "") (part "-LED")))
    (comp (ref "P1")
      (value "HEADER PAD 3 PIN")
      (fields
        (field (name "Manufacturer Part") "Female headerHDR1X8-2.54")
        (field (name "Manufacturer") "BOOMELE")
      )
      (libsource (lib "") (part "HEADER PAD 3 PIN"))
    )
    (comp (ref "Q1")
      (value "BC557")
      (fields (field (name "Manufacturer") "CJ(江苏长电/长晶)"))
      (libsource (lib "") (part "BC557"))
    )
    (comp (ref "U10") (value "~") (libsource (lib "") (part "EM-18")))
    (comp (ref "D1")
      (value "1N4007")
      (fields (field (name "Manufacturer") "ST(先科)"))
      (libsource (lib "") (part "1N4007"))
    )
    (comp (ref "Q2")
      (value "BC548B")
      (fields (field (name "Manufacturer Part") "BC548") (field (name "Manufacturer") "CJ(江苏长电/长晶)"))
      (libsource (lib "") (part "BC548B"))
    )
    (comp (ref "R1") (value "1000Ω") (libsource (lib "") (part "330Ω RESISTANCE")))
    (comp (ref "R2") (value "1000Ω") (libsource (lib "") (part "330Ω RESISTANCE")))
    (comp (ref "R3") (value "1000Ω") (libsource (lib "") (part "330Ω RESISTANCE_1")))
    (comp (ref "U11")
      (value "~")
      (fields (field (name "Manufacturer Part") "SRD-05VDC-SL-C") (field (name "Manufacturer") "松乐"))
      (libsource (lib "") (part "SRD-05VDC-SL-C"))
    )
    (comp (ref "U12") (value "LED") (libsource (lib "") (part "-LED")))
    (comp (ref "U13") (value "LED") (libsource (lib "") (part "-LED")))
    (comp (ref "U14") (value "3PIN TERMINALBOCK") (libsource (lib "") (part "3PIN TERMINALBOCK")))
    (comp (ref "U15")
      (value "3 PIN MALE JAMPER")
      (fields (field (name "Manufacturer Part") "1x3 pin header") (field (name "Manufacturer") "NA"))
      (libsource (lib "") (part "3 PIN MALE JAMPER"))
    )
    (comp (ref "LCD1") (value "LCD 16x2") (libsource (lib "") (part "LCD 16x2")))
    (comp (ref "U16")
      (value "6-pin male-male header")
      (fields (field (name "Manufacturer Part") "87224-5") (field (name "Manufacturer") "TE Connectivity"))
      (libsource (lib "") (part "6-pin male-male header"))
    )
    (comp (ref "U17") (value "1k potentiometer") (libsource (lib "") (part "Pot_blue")))
    (comp (ref "U18")
      (value "2-PIN-MALE HEADER")
      (fields (field (name "Manufacturer Part") "87224-5") (field (name "Manufacturer") "TE Connectivity"))
      (libsource (lib "") (part "2-PIN-MALE HEADER"))
    )
    (comp (ref "+") (value "T-2") (libsource (lib "") (part "TERMINAL-BLOCK-3.5MM-2-PIN-LONG-PAD_1")))
    (comp (ref "-") (value "T-1") (libsource (lib "") (part "TERMINAL-BLOCK-3.5MM-2-PIN-LONG-PAD")))
    (comp (ref "1R")
      (value "NO")
      (fields (field (name "Manufacturer") "Huaxing Mechanical-Elec."))
      (libsource (lib "") (part "1/4W-2.2KΩ±1%"))
    )
    (comp (ref "2.1K")
      (value "NO")
      (fields (field (name "Manufacturer") "Huaxing Mechanical-Elec."))
      (libsource (lib "") (part "1/4W-2.2KΩ±1%_1"))
    )
    (comp (ref "BUZZER2")
      (value "BUZZER")
      (fields (field (name "Manufacturer Part") "buzzer"))
      (libsource (lib "") (part "BUZZER"))
    )
    (comp (ref "C3")
      (value "104")
      (fields
        (field (name "Manufacturer Part") "Suppression Capacitor222M/250V")
        (field (name "Manufacturer") "ReliaPro")
      )
      (libsource (lib "") (part "104nf"))
    )
    (comp (ref "C4")
      (value "100UF/16V")
      (fields (field (name "Manufacturer Part") "100uF/16V"))
      (libsource (lib "") (part "100UF/16V"))
    )
    (comp (ref "CN2") (value "PINHEADER-6PIN6") (libsource (lib "") (part "PINHEADER-6PIN6")))
    (comp (ref "D2")
      (value "1N4007")
      (fields (field (name "Manufacturer") "ST(先科)"))
      (libsource (lib "") (part "1N4007"))
    )
    (comp (ref "LCD2") (value "LCD 16x2") (libsource (lib "") (part "LCD 16x2")))
    (comp (ref "LED1") (value "NO") (libsource (lib "") (part "-LED_1")))
    (comp (ref "P2")
      (value "HEADER PAD 3 PIN")
      (fields
        (field (name "Manufacturer Part") "Female headerHDR1X8-2.54")
        (field (name "Manufacturer") "BOOMELE")
      )
      (libsource (lib "") (part "HEADER PAD 3 PIN"))
    )
    (comp (ref "Q3")
      (value "BC557")
      (fields (field (name "Manufacturer") "CJ(江苏长电/长晶)"))
      (libsource (lib "") (part "BC557"))
    )
    (comp (ref "Q4")
      (value "BC548B")
      (fields (field (name "Manufacturer Part") "BC548") (field (name "Manufacturer") "CJ(江苏长电/长晶)"))
      (libsource (lib "") (part "BC548B"))
    )
    (comp (ref "R4") (value "1000Ω") (libsource (lib "") (part "330Ω RESISTANCE_1")))
    (comp (ref "R5") (value "1000Ω") (libsource (lib "") (part "330Ω RESISTANCE")))
    (comp (ref "R6") (value "1000Ω") (libsource (lib "") (part "330Ω RESISTANCE")))
    (comp (ref "U19") (value "NO") (libsource (lib "") (part "ESO_SPST_Momentary")))
    (comp (ref "U20") (value "NO") (libsource (lib "") (part "ESO_SPST_Momentary")))
    (comp (ref "U21") (value "NO") (libsource (lib "") (part "ESO_SPST_Momentary")))
    (comp (ref "U22") (value "NO") (libsource (lib "") (part "ESO_SPST_Momentary")))
    (comp (ref "U23") (value "NO") (libsource (lib "") (part "ESO_SPST_Momentary")))
    (comp (ref "U24") (value "NO") (libsource (lib "") (part "ESO_SPST_Momentary")))
    (comp (ref "U25") (value "NO") (libsource (lib "") (part "ESO_SPST_Momentary")))
    (comp (ref "U26") (value "NO") (libsource (lib "") (part "ESO_SPST_Momentary")))
    (comp (ref "U27") (value "NO") (libsource (lib "") (part "ESO_SPST_Momentary")))
    (comp (ref "U28") (value "NO") (libsource (lib "") (part "EM-18")))
    (comp (ref "U29")
      (value "3 PIN MALE JAMPER")
      (fields (field (name "Manufacturer Part") "1x3 pin header") (field (name "Manufacturer") "NA"))
      (libsource (lib "") (part "3 PIN MALE JAMPER"))
    )
    (comp (ref "U30") (value "3PIN TERMINALBOCK") (libsource (lib "") (part "3PIN TERMINALBOCK")))
    (comp (ref "U31") (value "LED") (libsource (lib "") (part "-LED")))
    (comp (ref "U32") (value "LED") (libsource (lib "") (part "-LED")))
    (comp (ref "U33")
      (value "NO")
      (fields (field (name "Manufacturer Part") "SRD-05VDC-SL-C") (field (name "Manufacturer") "松乐"))
      (libsource (lib "") (part "SRD-05VDC-SL-C"))
    )
    (comp (ref "U34")
      (value "2-PIN-MALE HEADER")
      (fields (field (name "Manufacturer Part") "87224-5") (field (name "Manufacturer") "TE Connectivity"))
      (libsource (lib "") (part "2-PIN-MALE HEADER"))
    )
    (comp (ref "U35")
      (value "6-pin male-male header")
      (fields (field (name "Manufacturer Part") "87224-5") (field (name "Manufacturer") "TE Connectivity"))
      (libsource (lib "") (part "6-pin male-male header"))
    )
    (comp (ref "U36") (value "1k potentiometer") (libsource (lib "") (part "Pot_blue")))
    (comp (ref "U37") (value "ARDUINO UNO GD32") (libsource (lib "") (part "ARDUINO UNO GD32")))
    (comp (ref "CN3") (value "PINHEADER-6PIN6") (libsource (lib "") (part "PINHEADER-6PIN6")))
    (comp (ref "U38") (value "NO") (libsource (lib "") (part "ESO_SPST_Momentary")))
    (comp (ref "U39") (value "NO") (libsource (lib "") (part "ESO_SPST_Momentary")))
    (comp (ref "U40") (value "NO") (libsource (lib "") (part "ESO_SPST_Momentary")))
    (comp (ref "U41") (value "NO") (libsource (lib "") (part "ESO_SPST_Momentary")))
    (comp (ref "U42") (value "NO") (libsource (lib "") (part "ESO_SPST_Momentary")))
    (comp (ref "U43") (value "NO") (libsource (lib "") (part "ESO_SPST_Momentary")))
    (comp (ref "U44") (value "NO") (libsource (lib "") (part "ESO_SPST_Momentary")))
    (comp (ref "U45") (value "NO") (libsource (lib "") (part "ESO_SPST_Momentary")))
    (comp (ref "U46") (value "NO") (libsource (lib "") (part "ESO_SPST_Momentary")))
    (comp (ref "U47") (value "ARDUINO UNO GD32") (libsource (lib "") (part "ARDUINO UNO GD32")))
    (comp (ref "LCD3") (value "LCD 16x2") (libsource (lib "") (part "LCD 16x2")))
    (comp (ref "U48") (value "1k potentiometer") (libsource (lib "") (part "Pot_blue")))
    (comp (ref "U49")
      (value "6-pin male-male header")
      (fields (field (name "Manufacturer Part") "87224-5") (field (name "Manufacturer") "TE Connectivity"))
      (libsource (lib "") (part "6-pin male-male header"))
    )
    (comp (ref "U50")
      (value "2-PIN-MALE HEADER")
      (fields (field (name "Manufacturer Part") "87224-5") (field (name "Manufacturer") "TE Connectivity"))
      (libsource (lib "") (part "2-PIN-MALE HEADER"))
    )
    (comp (ref "U51") (value "ARDUINO UNO GD32") (libsource (lib "") (part "ARDUINO UNO GD32")))
    (comp (ref "2.3K")
      (value "NO")
      (fields (field (name "Manufacturer") "Huaxing Mechanical-Elec."))
      (libsource (lib "") (part "1/4W-2.2KΩ±1%_1"))
    )
    (comp (ref "2R")
      (value "NO")
      (fields (field (name "Manufacturer") "Huaxing Mechanical-Elec."))
      (libsource (lib "") (part "1/4W-2.2KΩ±1%"))
    )
    (comp (ref "BUZZER3")
      (value "BUZZER")
      (fields (field (name "Manufacturer Part") "buzzer"))
      (libsource (lib "") (part "BUZZER"))
    )
    (comp (ref "C5")
      (value "100UF/16V")
      (fields (field (name "Manufacturer Part") "100uF/16V"))
      (libsource (lib "") (part "100UF/16V"))
    )
    (comp (ref "C6")
      (value "104")
      (fields
        (field (name "Manufacturer Part") "Suppression Capacitor222M/250V")
        (field (name "Manufacturer") "ReliaPro")
      )
      (libsource (lib "") (part "104nf"))
    )
    (comp (ref "LED2") (value "NO") (libsource (lib "") (part "-LED")))
    (comp (ref "P3")
      (value "HEADER PAD 3 PIN")
      (fields
        (field (name "Manufacturer Part") "Female headerHDR1X8-2.54")
        (field (name "Manufacturer") "BOOMELE")
      )
      (libsource (lib "") (part "HEADER PAD 3 PIN"))
    )
    (comp (ref "Q5")
      (value "BC557")
      (fields (field (name "Manufacturer") "CJ(江苏长电/长晶)"))
      (libsource (lib "") (part "BC557"))
    )
    (comp (ref "U52") (value "ARDUINO UNO GD32") (libsource (lib "") (part "ARDUINO UNO GD32")))
    (comp (ref "U53") (value "NO") (libsource (lib "") (part "EM-18")))
    (comp (ref "D3")
      (value "1N4007")
      (fields (field (name "Manufacturer") "ST(先科)"))
      (libsource (lib "") (part "1N4007"))
    )
    (comp (ref "Q6")
      (value "BC548B")
      (fields (field (name "Manufacturer Part") "BC548") (field (name "Manufacturer") "CJ(江苏长电/长晶)"))
      (libsource (lib "") (part "BC548B"))
    )
    (comp (ref "R7") (value "1000Ω") (libsource (lib "") (part "330Ω RESISTANCE")))
    (comp (ref "R8") (value "1000Ω") (libsource (lib "") (part "330Ω RESISTANCE")))
    (comp (ref "R9") (value "1000Ω") (libsource (lib "") (part "330Ω RESISTANCE_1")))
    (comp (ref "U54") (value "ARDUINO UNO GD32") (libsource (lib "") (part "ARDUINO UNO GD32")))
    (comp (ref "U55")
      (value "NO")
      (fields (field (name "Manufacturer Part") "SRD-05VDC-SL-C") (field (name "Manufacturer") "松乐"))
      (libsource (lib "") (part "SRD-05VDC-SL-C"))
    )
    (comp (ref "U56") (value "LED") (libsource (lib "") (part "-LED")))
    (comp (ref "U57") (value "LED") (libsource (lib "") (part "-LED")))
    (comp (ref "U58")
      (value "3 PIN MALE JAMPER")
      (fields (field (name "Manufacturer Part") "1x3 pin header") (field (name "Manufacturer") "NA"))
      (libsource (lib "") (part "3 PIN MALE JAMPER"))
    )
    (comp (ref "U59") (value "3PIN TERMINALBOCK") (libsource (lib "") (part "3PIN TERMINALBOCK")))
  )
  (nets
    (net (code "1") (name "C1") (class "Default")
      (node (ref "CN2") (pin "4") (pinfunction "C1_4") (pintype "input"))
      (node (ref "CN3") (pin "4") (pinfunction "C1_4") (pintype "input"))
      (node (ref "U19") (pin "1") (pinfunction "1_1") (pintype "unspecified"))
      (node (ref "U19") (pin "2") (pinfunction "2_2") (pintype "unspecified"))
      (node (ref "U22") (pin "1") (pinfunction "1_1") (pintype "unspecified"))
      (node (ref "U22") (pin "2") (pinfunction "2_2") (pintype "unspecified"))
      (node (ref "U27") (pin "1") (pinfunction "1_1") (pintype "unspecified"))
      (node (ref "U27") (pin "2") (pinfunction "2_2") (pintype "unspecified"))
      (node (ref "U37") (pin "9") (pinfunction "D8_9") (pintype "unspecified"))
      (node (ref "U38") (pin "1") (pinfunction "1_1") (pintype "unspecified"))
      (node (ref "U38") (pin "2") (pinfunction "2_2") (pintype "unspecified"))
      (node (ref "U43") (pin "1") (pinfunction "1_1") (pintype "unspecified"))
      (node (ref "U43") (pin "2") (pinfunction "2_2") (pintype "unspecified"))
      (node (ref "U46") (pin "1") (pinfunction "1_1") (pintype "unspecified"))
      (node (ref "U46") (pin "2") (pinfunction "2_2") (pintype "unspecified"))
      (node (ref "U47") (pin "9") (pinfunction "D8_9") (pintype "unspecified"))
    )
    (net (code "2") (name "C2") (class "Default")
      (node (ref "CN2") (pin "5") (pinfunction "C2_5") (pintype "input"))
      (node (ref "CN3") (pin "5") (pinfunction "C2_5") (pintype "input"))
      (node (ref "U20") (pin "1") (pinfunction "1_1") (pintype "unspecified"))
      (node (ref "U20") (pin "2") (pinfunction "2_2") (pintype "unspecified"))
      (node (ref "U23") (pin "1") (pinfunction "1_1") (pintype "unspecified"))
      (node (ref "U23") (pin "2") (pinfunction "2_2") (pintype "unspecified"))
      (node (ref "U26") (pin "1") (pinfunction "1_1") (pintype "unspecified"))
      (node (ref "U26") (pin "2") (pinfunction "2_2") (pintype "unspecified"))
      (node (ref "U37") (pin "10") (pinfunction "D9_10") (pintype "unspecified"))
      (node (ref "U39") (pin "1") (pinfunction "1_1") (pintype "unspecified"))
      (node (ref "U39") (pin "2") (pinfunction "2_2") (pintype "unspecified"))
      (node (ref "U42") (pin "1") (pinfunction "1_1") (pintype "unspecified"))
      (node (ref "U42") (pin "2") (pinfunction "2_2") (pintype "unspecified"))
      (node (ref "U45") (pin "1") (pinfunction "1_1") (pintype "unspecified"))
      (node (ref "U45") (pin "2") (pinfunction "2_2") (pintype "unspecified"))
      (node (ref "U47") (pin "10") (pinfunction "D9_10") (pintype "unspecified"))
    )
    (net (code "3") (name "C3") (class "Default")
      (node (ref "CN2") (pin "6") (pinfunction "C3_6") (pintype "input"))
      (node (ref "CN3") (pin "6") (pinfunction "C3_6") (pintype "input"))
      (node (ref "U21") (pin "1") (pinfunction "1_1") (pintype "unspecified"))
      (node (ref "U21") (pin "2") (pinfunction "2_2") (pintype "unspecified"))
      (node (ref "U24") (pin "1") (pinfunction "1_1") (pintype "unspecified"))
      (node (ref "U24") (pin "2") (pinfunction "2_2") (pintype "unspecified"))
      (node (ref "U25") (pin "1") (pinfunction "1_1") (pintype "unspecified"))
      (node (ref "U25") (pin "2") (pinfunction "2_2") (pintype "unspecified"))
      (node (ref "U37") (pin "11") (pinfunction "D10_11") (pintype "unspecified"))
      (node (ref "U40") (pin "1") (pinfunction "1_1") (pintype "unspecified"))
      (node (ref "U40") (pin "2") (pinfunction "2_2") (pintype "unspecified"))
      (node (ref "U41") (pin "1") (pinfunction "1_1") (pintype "unspecified"))
      (node (ref "U41") (pin "2") (pinfunction "2_2") (pintype "unspecified"))
      (node (ref "U44") (pin "1") (pinfunction "1_1") (pintype "unspecified"))
      (node (ref "U44") (pin "2") (pinfunction "2_2") (pintype "unspecified"))
      (node (ref "U47") (pin "11") (pinfunction "D10_11") (pintype "unspecified"))
    )
    (net (code "4") (name "COM") (class "Default")
      (node (ref "U11") (pin "3") (pinfunction "COM_3") (pintype "unspecified"))
      (node (ref "U14") (pin "2") (pinfunction "2_2") (pintype "unspecified"))
      (node (ref "U30") (pin "2") (pinfunction "2_2") (pintype "unspecified"))
      (node (ref "U33") (pin "3") (pinfunction "COM_3") (pintype "unspecified"))
      (node (ref "U37") (pin "25") (pinfunction "VIN_25") (pintype "passive"))
      (node (ref "U54") (pin "25") (pinfunction "VIN_25") (pintype "passive"))
      (node (ref "U55") (pin "3") (pinfunction "COM_3") (pintype "unspecified"))
      (node (ref "U59") (pin "2") (pinfunction "2_2") (pintype "unspecified"))
    )
    (net (code "5") (name "D4") (class "Default")
      (node (ref "LCD2") (pin "11") (pinfunction "DB4_11") (pintype "unspecified"))
      (node (ref "LCD3") (pin "11") (pinfunction "DB4_11") (pintype "unspecified"))
      (node (ref "U35") (pin "D4") (pinfunction "4_D4") (pintype "unspecified"))
      (node (ref "U37") (pin "21") (pinfunction "A3_21") (pintype "unspecified"))
      (node (ref "U49") (pin "D4") (pinfunction "4_D4") (pintype "unspecified"))
      (node (ref "U51") (pin "21") (pinfunction "A3_21") (pintype "unspecified"))
    )
    (net (code "6") (name "D5") (class "Default")
      (node (ref "LCD2") (pin "12") (pinfunction "DB5_12") (pintype "unspecified"))
      (node (ref "LCD3") (pin "12") (pinfunction "DB5_12") (pintype "unspecified"))
      (node (ref "U35") (pin "D5") (pinfunction "3_D5") (pintype "unspecified"))
      (node (ref "U37") (pin "22") (pinfunction "A2_22") (pintype "unspecified"))
      (node (ref "U49") (pin "D5") (pinfunction "3_D5") (pintype "unspecified"))
      (node (ref "U51") (pin "22") (pinfunction "A2_22") (pintype "unspecified"))
    )
    (net (code "7") (name "D6") (class "Default")
      (node (ref "LCD2") (pin "13") (pinfunction "DB6_13") (pintype "unspecified"))
      (node (ref "LCD3") (pin "13") (pinfunction "DB6_13") (pintype "unspecified"))
      (node (ref "U35") (pin "D6") (pinfunction "2_D6") (pintype "unspecified"))
      (node (ref "U37") (pin "23") (pinfunction "A1_23") (pintype "unspecified"))
      (node (ref "U49") (pin "D6") (pinfunction "2_D6") (pintype "unspecified"))
      (node (ref "U51") (pin "23") (pinfunction "A1_23") (pintype "unspecified"))
    )
    (net (code "8") (name "D7") (class "Default")
      (node (ref "LCD2") (pin "14") (pinfunction "DB7_14") (pintype "unspecified"))
      (node (ref "LCD3") (pin "14") (pinfunction "DB7_14") (pintype "unspecified"))
      (node (ref "U35") (pin "D7") (pinfunction "1_D7") (pintype "unspecified"))
      (node (ref "U37") (pin "24") (pinfunction "A0_24") (pintype "unspecified"))
      (node (ref "U49") (pin "D7") (pinfunction "1_D7") (pintype "unspecified"))
      (node (ref "U51") (pin "24") (pinfunction "A0_24") (pintype "unspecified"))
    )
    (net (code "9") (name "E") (class "Default")
      (node (ref "LCD2") (pin "6") (pinfunction "E_6") (pintype "unspecified"))
      (node (ref "LCD3") (pin "6") (pinfunction "E_6") (pintype "unspecified"))
      (node (ref "U35") (pin "E") (pinfunction "5_E") (pintype "unspecified"))
      (node (ref "U37") (pin "20") (pinfunction "A4_20") (pintype "unspecified"))
      (node (ref "U49") (pin "E") (pinfunction "5_E") (pintype "unspecified"))
      (node (ref "U51") (pin "20") (pinfunction "A4_20") (pintype "unspecified"))
    )
    (net (code "10") (name "GND") (class "Default")
      (node (ref "BUZZER1") (pin "1") (pinfunction "-_1") (pintype "unspecified"))
      (node (ref "BUZZER2") (pin "1") (pinfunction "-_1") (pintype "unspecified"))
      (node (ref "BUZZER3") (pin "1") (pinfunction "-_1") (pintype "unspecified"))
      (node (ref "C1") (pin "2") (pinfunction "2_2") (pintype "input"))
      (node (ref "C2") (pin "1") (pinfunction "1_1") (pintype "input"))
      (node (ref "C3") (pin "1") (pinfunction "1_1") (pintype "input"))
      (node (ref "C4") (pin "2") (pinfunction "2_2") (pintype "input"))
      (node (ref "C5") (pin "2") (pinfunction "2_2") (pintype "input"))
      (node (ref "C6") (pin "1") (pinfunction "1_1") (pintype "input"))
      (node (ref "LCD2") (pin "1") (pinfunction "Vss_1") (pintype "unspecified"))
      (node (ref "LCD2") (pin "16") (pinfunction "K_16") (pintype "unspecified"))
      (node (ref "LCD2") (pin "5") (pinfunction "RW_5") (pintype "unspecified"))
      (node (ref "LCD3") (pin "1") (pinfunction "Vss_1") (pintype "unspecified"))
      (node (ref "LCD3") (pin "16") (pinfunction "K_16") (pintype "unspecified"))
      (node (ref "LCD3") (pin "5") (pinfunction "RW_5") (pintype "unspecified"))
      (node (ref "LED") (pin "CATHODE") (pinfunction "CATHODE_CATHODE") (pintype "unspecified"))
      (node (ref "LED1") (pin "CATHODE") (pinfunction "CATHODE_CATHODE") (pintype "unspecified"))
      (node (ref "LED2") (pin "CATHODE") (pinfunction "CATHODE_CATHODE") (pintype "unspecified"))
      (node (ref "P1") (pin "2") (pinfunction "2_2") (pintype "input"))
      (node (ref "P2") (pin "2") (pinfunction "2_2") (pintype "input"))
      (node (ref "P3") (pin "2") (pinfunction "2_2") (pintype "input"))
      (node (ref "Q2") (pin "3") (pinfunction "E_3") (pintype "unspecified"))
      (node (ref "Q4") (pin "3") (pinfunction "E_3") (pintype "unspecified"))
      (node (ref "Q6") (pin "3") (pinfunction "E_3") (pintype "unspecified"))
      (node (ref "U10") (pin "3") (pinfunction "GND_3") (pintype "unspecified"))
      (node (ref "U13") (pin "CATHODE") (pinfunction "CATHODE_CATHODE") (pintype "unspecified"))
      (node (ref "U15") (pin "2") (pinfunction "2_2") (pintype "unspecified"))
      (node (ref "U28") (pin "3") (pinfunction "GND_3") (pintype "unspecified"))
      (node (ref "U29") (pin "2") (pinfunction "2_2") (pintype "unspecified"))
      (node (ref "U31") (pin "CATHODE") (pinfunction "CATHODE_CATHODE") (pintype "unspecified"))
      (node (ref "U34") (pin "GND") (pinfunction "2_GND") (pintype "unspecified"))
      (node (ref "U36") (pin "1") (pinfunction "1_1") (pintype "input"))
      (node (ref "U37") (pin "26") (pinfunction "GND1_26") (pintype "passive"))
      (node (ref "U48") (pin "1") (pinfunction "1_1") (pintype "input"))
      (node (ref "U50") (pin "GND") (pinfunction "2_GND") (pintype "unspecified"))
      (node (ref "U51") (pin "26") (pinfunction "GND1_26") (pintype "passive"))
      (node (ref "U52") (pin "26") (pinfunction "GND1_26") (pintype "passive"))
      (node (ref "U53") (pin "3") (pinfunction "GND_3") (pintype "unspecified"))
      (node (ref "U54") (pin "26") (pinfunction "GND1_26") (pintype "passive"))
      (node (ref "U57") (pin "CATHODE") (pinfunction "CATHODE_CATHODE") (pintype "unspecified"))
      (node (ref "U58") (pin "2") (pinfunction "2_2") (pintype "unspecified"))
    )
    (net (code "11") (name "IN") (class "Default")
      (node (ref "R3") (pin "2") (pinfunction "2_2") (pintype "unspecified"))
      (node (ref "R4") (pin "2") (pinfunction "2_2") (pintype "unspecified"))
      (node (ref "R9") (pin "2") (pinfunction "2_2") (pintype "unspecified"))
      (node (ref "U15") (pin "3") (pinfunction "3_3") (pintype "unspecified"))
      (node (ref "U29") (pin "3") (pinfunction "3_3") (pintype "unspecified"))
      (node (ref "U37") (pin "3") (pinfunction "D2_3") (pintype "unspecified"))
      (node (ref "U54") (pin "3") (pinfunction "D2_3") (pintype "unspecified"))
      (node (ref "U58") (pin "3") (pinfunction "3_3") (pintype "unspecified"))
    )
    (net (code "12") (name "NC") (class "Default")
      (node (ref "U11") (pin "4") (pinfunction "NC_4") (pintype "unspecified"))
      (node (ref "U14") (pin "1") (pinfunction "1_1") (pintype "unspecified"))
      (node (ref "U30") (pin "1") (pinfunction "1_1") (pintype "unspecified"))
      (node (ref "U33") (pin "4") (pinfunction "NC_4") (pintype "unspecified"))
      (node (ref "U55") (pin "4") (pinfunction "NC_4") (pintype "unspecified"))
      (node (ref "U59") (pin "1") (pinfunction "1_1") (pintype "unspecified"))
    )
    (net (code "13") (name "NO") (class "Default")
      (node (ref "U14") (pin "3") (pinfunction "3_3") (pintype "unspecified"))
      (node (ref "U30") (pin "3") (pinfunction "3_3") (pintype "unspecified"))
      (node (ref "U59") (pin "3") (pinfunction "3_3") (pintype "unspecified"))
    )
    (net (code "14") (name "Net-(1R-Pad2)") (class "Default")
      (node (ref "1R") (pin "2") (pinfunction "2_2") (pintype "unspecified"))
      (node (ref "LED1") (pin "ANODE") (pinfunction "ANODE_ANODE") (pintype "unspecified"))
    )
    (net (code "15") (name "Net-(2R-Pad2)") (class "Default")
      (node (ref "2R") (pin "2") (pinfunction "2_2") (pintype "unspecified"))
      (node (ref "LED2") (pin "ANODE") (pinfunction "ANODE_ANODE") (pintype "unspecified"))
    )
    (net (code "16") (name "Net-(470R-Pad2)") (class "Default")
      (node (ref "470R") (pin "2") (pinfunction "2_2") (pintype "unspecified"))
      (node (ref "LED") (pin "ANODE") (pinfunction "ANODE_ANODE") (pintype "unspecified"))
    )
    (net (code "17") (name "Net-(BUZZER1-+)") (class "Default")
      (node (ref "470R") (pin "1") (pinfunction "1_1") (pintype "unspecified"))
      (node (ref "BUZZER1") (pin "2") (pinfunction "+_2") (pintype "unspecified"))
      (node (ref "Q1") (pin "1") (pinfunction "C_1") (pintype "unspecified"))
    )
    (net (code "18") (name "Net-(BUZZER2-+)") (class "Default")
      (node (ref "1R") (pin "1") (pinfunction "1_1") (pintype "unspecified"))
      (node (ref "BUZZER2") (pin "2") (pinfunction "+_2") (pintype "unspecified"))
      (node (ref "Q3") (pin "1") (pinfunction "C_1") (pintype "unspecified"))
    )
    (net (code "19") (name "Net-(BUZZER3-+)") (class "Default")
      (node (ref "2R") (pin "1") (pinfunction "1_1") (pintype "unspecified"))
      (node (ref "BUZZER3") (pin "2") (pinfunction "+_2") (pintype "unspecified"))
      (node (ref "Q5") (pin "1") (pinfunction "C_1") (pintype "unspecified"))
    )
    (net (code "20") (name "Net-(CN1-C1)") (class "Default")
      (node (ref "CN1") (pin "4") (pinfunction "C1_4") (pintype "input"))
      (node (ref "U1") (pin "1") (pinfunction "1_1") (pintype "unspecified"))
      (node (ref "U1") (pin "2") (pinfunction "2_2") (pintype "unspecified"))
      (node (ref "U6") (pin "1") (pinfunction "1_1") (pintype "unspecified"))
      (node (ref "U6") (pin "2") (pinfunction "2_2") (pintype "unspecified"))
      (node (ref "U9") (pin "1") (pinfunction "1_1") (pintype "unspecified"))
      (node (ref "U9") (pin "2") (pinfunction "2_2") (pintype "unspecified"))
    )
    (net (code "21") (name "Net-(CN1-C2)") (class "Default")
      (node (ref "CN1") (pin "5") (pinfunction "C2_5") (pintype "input"))
      (node (ref "U2") (pin "1") (pinfunction "1_1") (pintype "unspecified"))
      (node (ref "U2") (pin "2") (pinfunction "2_2") (pintype "unspecified"))
      (node (ref "U5") (pin "1") (pinfunction "1_1") (pintype "unspecified"))
      (node (ref "U5") (pin "2") (pinfunction "2_2") (pintype "unspecified"))
      (node (ref "U8") (pin "1") (pinfunction "1_1") (pintype "unspecified"))
      (node (ref "U8") (pin "2") (pinfunction "2_2") (pintype "unspecified"))
    )
    (net (code "22") (name "Net-(CN1-C3)") (class "Default")
      (node (ref "CN1") (pin "6") (pinfunction "C3_6") (pintype "input"))
      (node (ref "U3") (pin "1") (pinfunction "1_1") (pintype "unspecified"))
      (node (ref "U3") (pin "2") (pinfunction "2_2") (pintype "unspecified"))
      (node (ref "U4") (pin "1") (pinfunction "1_1") (pintype "unspecified"))
      (node (ref "U4") (pin "2") (pinfunction "2_2") (pintype "unspecified"))
      (node (ref "U7") (pin "1") (pinfunction "1_1") (pintype "unspecified"))
      (node (ref "U7") (pin "2") (pinfunction "2_2") (pintype "unspecified"))
    )
    (net (code "23") (name "Net-(CN1-R1)") (class "Default")
      (node (ref "CN1") (pin "1") (pinfunction "R1_1") (pintype "input"))
      (node (ref "U1") (pin "3") (pinfunction "3_3") (pintype "unspecified"))
      (node (ref "U1") (pin "4") (pinfunction "4_4") (pintype "unspecified"))
      (node (ref "U2") (pin "3") (pinfunction "3_3") (pintype "unspecified"))
      (node (ref "U2") (pin "4") (pinfunction "4_4") (pintype "unspecified"))
      (node (ref "U3") (pin "3") (pinfunction "3_3") (pintype "unspecified"))
      (node (ref "U3") (pin "4") (pinfunction "4_4") (pintype "unspecified"))
    )
    (net (code "24") (name "Net-(CN1-R2)") (class "Default")
      (node (ref "CN1") (pin "2") (pinfunction "R2_2") (pintype "input"))
      (node (ref "U4") (pin "3") (pinfunction "3_3") (pintype "unspecified"))
      (node (ref "U4") (pin "4") (pinfunction "4_4") (pintype "unspecified"))
      (node (ref "U5") (pin "3") (pinfunction "3_3") (pintype "unspecified"))
      (node (ref "U5") (pin "4") (pinfunction "4_4") (pintype "unspecified"))
      (node (ref "U6") (pin "3") (pinfunction "3_3") (pintype "unspecified"))
      (node (ref "U6") (pin "4") (pinfunction "4_4") (pintype "unspecified"))
    )
    (net (code "25") (name "Net-(CN1-R3)") (class "Default")
      (node (ref "CN1") (pin "3") (pinfunction "R3_3") (pintype "input"))
      (node (ref "U7") (pin "3") (pinfunction "3_3") (pintype "unspecified"))
      (node (ref "U7") (pin "4") (pinfunction "4_4") (pintype "unspecified"))
      (node (ref "U8") (pin "3") (pinfunction "3_3") (pintype "unspecified"))
      (node (ref "U8") (pin "4") (pinfunction "4_4") (pintype "unspecified"))
      (node (ref "U9") (pin "3") (pinfunction "3_3") (pintype "unspecified"))
      (node (ref "U9") (pin "4") (pinfunction "4_4") (pintype "unspecified"))
    )
    (net (code "26") (name "Net-(D1-A)") (class "Default")
      (node (ref "D1") (pin "2") (pinfunction "A_2") (pintype "unspecified"))
      (node (ref "Q2") (pin "1") (pinfunction "C_1") (pintype "unspecified"))
      (node (ref "U11") (pin "1") (pinfunction "OT_1") (pintype "unspecified"))
      (node (ref "U12") (pin "CATHODE") (pinfunction "CATHODE_CATHODE") (pintype "unspecified"))
    )
    (net (code "27") (name "Net-(D2-A)") (class "Default")
      (node (ref "D2") (pin "2") (pinfunction "A_2") (pintype "unspecified"))
      (node (ref "Q4") (pin "1") (pinfunction "C_1") (pintype "unspecified"))
      (node (ref "U32") (pin "CATHODE") (pinfunction "CATHODE_CATHODE") (pintype "unspecified"))
      (node (ref "U33") (pin "1") (pinfunction "OT_1") (pintype "unspecified"))
    )
    (net (code "28") (name "Net-(D3-A)") (class "Default")
      (node (ref "D3") (pin "2") (pinfunction "A_2") (pintype "unspecified"))
      (node (ref "Q6") (pin "1") (pinfunction "C_1") (pintype "unspecified"))
      (node (ref "U55") (pin "1") (pinfunction "OT_1") (pintype "unspecified"))
      (node (ref "U56") (pin "CATHODE") (pinfunction "CATHODE_CATHODE") (pintype "unspecified"))
    )
    (net (code "29") (name "Net-(LCD1-A)") (class "Default")
      (node (ref "LCD1") (pin "15") (pinfunction "A_15") (pintype "unspecified"))
      (node (ref "LCD1") (pin "2") (pinfunction "Vdd_2") (pintype "unspecified"))
      (node (ref "U17") (pin "3") (pinfunction "2_3") (pintype "input"))
      (node (ref "U18") (pin "1") (pinfunction "1_1") (pintype "unspecified"))
    )
    (net (code "30") (name "Net-(LCD1-DB4)") (class "Default")
      (node (ref "LCD1") (pin "11") (pinfunction "DB4_11") (pintype "unspecified"))
      (node (ref "U16") (pin "4") (pinfunction "4_4") (pintype "unspecified"))
    )
    (net (code "31") (name "Net-(LCD1-DB5)") (class "Default")
      (node (ref "LCD1") (pin "12") (pinfunction "DB5_12") (pintype "unspecified"))
      (node (ref "U16") (pin "3") (pinfunction "3_3") (pintype "unspecified"))
    )
    (net (code "32") (name "Net-(LCD1-DB6)") (class "Default")
      (node (ref "LCD1") (pin "13") (pinfunction "DB6_13") (pintype "unspecified"))
      (node (ref "U16") (pin "2") (pinfunction "2_2") (pintype "unspecified"))
    )
    (net (code "33") (name "Net-(LCD1-DB7)") (class "Default")
      (node (ref "LCD1") (pin "14") (pinfunction "DB7_14") (pintype "unspecified"))
      (node (ref "U16") (pin "1") (pinfunction "1_1") (pintype "unspecified"))
    )
    (net (code "34") (name "Net-(LCD1-E)") (class "Default")
      (node (ref "LCD1") (pin "6") (pinfunction "E_6") (pintype "unspecified"))
      (node (ref "U16") (pin "5") (pinfunction "5_5") (pintype "unspecified"))
    )
    (net (code "35") (name "Net-(LCD1-K)") (class "Default")
      (node (ref "LCD1") (pin "1") (pinfunction "Vss_1") (pintype "unspecified"))
      (node (ref "LCD1") (pin "16") (pinfunction "K_16") (pintype "unspecified"))
      (node (ref "LCD1") (pin "5") (pinfunction "RW_5") (pintype "unspecified"))
      (node (ref "U17") (pin "1") (pinfunction "1_1") (pintype "input"))
      (node (ref "U18") (pin "2") (pinfunction "2_2") (pintype "unspecified"))
    )
    (net (code "36") (name "Net-(LCD1-RS)") (class "Default")
      (node (ref "LCD1") (pin "4") (pinfunction "RS_4") (pintype "unspecified"))
      (node (ref "U16") (pin "6") (pinfunction "6_6") (pintype "unspecified"))
    )
    (net (code "37") (name "Net-(LCD1-V0)") (class "Default")
      (node (ref "LCD1") (pin "3") (pinfunction "V0_3") (pintype "unspecified"))
      (node (ref "U17") (pin "2") (pinfunction "3_2") (pintype "input"))
    )
    (net (code "38") (name "Net-(LCD2-V0)") (class "Default")
      (node (ref "LCD2") (pin "3") (pinfunction "V0_3") (pintype "unspecified"))
      (node (ref "U36") (pin "2") (pinfunction "3_2") (pintype "input"))
    )
    (net (code "39") (name "Net-(LCD3-V0)") (class "Default")
      (node (ref "LCD3") (pin "3") (pinfunction "V0_3") (pintype "unspecified"))
      (node (ref "U48") (pin "2") (pinfunction "3_2") (pintype "input"))
    )
    (net (code "40") (name "Net-(Q1-B)") (class "Default")
      (node (ref "2.2K") (pin "2") (pinfunction "2_2") (pintype "unspecified"))
      (node (ref "Q1") (pin "2") (pinfunction "B_2") (pintype "unspecified"))
    )
    (net (code "41") (name "Net-(Q2-B)") (class "Default")
      (node (ref "Q2") (pin "2") (pinfunction "B_2") (pintype "unspecified"))
      (node (ref "R3") (pin "1") (pinfunction "1_1") (pintype "unspecified"))
    )
    (net (code "42") (name "Net-(Q3-B)") (class "Default")
      (node (ref "2.1K") (pin "2") (pinfunction "2_2") (pintype "unspecified"))
      (node (ref "Q3") (pin "2") (pinfunction "B_2") (pintype "unspecified"))
    )
    (net (code "43") (name "Net-(Q4-B)") (class "Default")
      (node (ref "Q4") (pin "2") (pinfunction "B_2") (pintype "unspecified"))
      (node (ref "R4") (pin "1") (pinfunction "1_1") (pintype "unspecified"))
    )
    (net (code "44") (name "Net-(Q5-B)") (class "Default")
      (node (ref "2.3K") (pin "2") (pinfunction "2_2") (pintype "unspecified"))
      (node (ref "Q5") (pin "2") (pinfunction "B_2") (pintype "unspecified"))
    )
    (net (code "45") (name "Net-(Q6-B)") (class "Default")
      (node (ref "Q6") (pin "2") (pinfunction "B_2") (pintype "unspecified"))
      (node (ref "R9") (pin "1") (pinfunction "1_1") (pintype "unspecified"))
    )
    (net (code "46") (name "Net-(R1-Pad1)") (class "Default")
      (node (ref "R1") (pin "1") (pinfunction "1_1") (pintype "unspecified"))
      (node (ref "U12") (pin "ANODE") (pinfunction "ANODE_ANODE") (pintype "unspecified"))
    )
    (net (code "47") (name "Net-(R2-Pad1)") (class "Default")
      (node (ref "R2") (pin "1") (pinfunction "1_1") (pintype "unspecified"))
      (node (ref "U13") (pin "ANODE") (pinfunction "ANODE_ANODE") (pintype "unspecified"))
    )
    (net (code "48") (name "Net-(R5-Pad1)") (class "Default")
      (node (ref "R5") (pin "1") (pinfunction "1_1") (pintype "unspecified"))
      (node (ref "U31") (pin "ANODE") (pinfunction "ANODE_ANODE") (pintype "unspecified"))
    )
    (net (code "49") (name "Net-(R6-Pad1)") (class "Default")
      (node (ref "R6") (pin "1") (pinfunction "1_1") (pintype "unspecified"))
      (node (ref "U32") (pin "ANODE") (pinfunction "ANODE_ANODE") (pintype "unspecified"))
    )
    (net (code "50") (name "Net-(R7-Pad1)") (class "Default")
      (node (ref "R7") (pin "1") (pinfunction "1_1") (pintype "unspecified"))
      (node (ref "U56") (pin "ANODE") (pinfunction "ANODE_ANODE") (pintype "unspecified"))
    )
    (net (code "51") (name "Net-(R8-Pad1)") (class "Default")
      (node (ref "R8") (pin "1") (pinfunction "1_1") (pintype "unspecified"))
      (node (ref "U57") (pin "ANODE") (pinfunction "ANODE_ANODE") (pintype "unspecified"))
    )
    (net (code "52") (name "Net-(U10-LED)") (class "Default")
      (node (ref "2.2K") (pin "1") (pinfunction "1_1") (pintype "unspecified"))
      (node (ref "U10") (pin "4") (pinfunction "LED_4") (pintype "unspecified"))
    )
    (net (code "53") (name "Net-(U28-LED)") (class "Default")
      (node (ref "2.1K") (pin "1") (pinfunction "1_1") (pintype "unspecified"))
      (node (ref "U28") (pin "4") (pinfunction "LED_4") (pintype "unspecified"))
    )
    (net (code "54") (name "Net-(U53-LED)") (class "Default")
      (node (ref "2.3K") (pin "1") (pinfunction "1_1") (pintype "unspecified"))
      (node (ref "U53") (pin "4") (pinfunction "LED_4") (pintype "unspecified"))
    )
    (net (code "55") (name "OUT") (class "Default")
      (node (ref "P1") (pin "3") (pinfunction "3_3") (pintype "input"))
      (node (ref "P2") (pin "3") (pinfunction "3_3") (pintype "input"))
      (node (ref "P3") (pin "3") (pinfunction "3_3") (pintype "input"))
      (node (ref "U10") (pin "8") (pinfunction "TX_8") (pintype "unspecified"))
      (node (ref "U28") (pin "8") (pinfunction "TX_8") (pintype "unspecified"))
      (node (ref "U37") (pin "1") (pinfunction "D0_1") (pintype "unspecified"))
      (node (ref "U52") (pin "1") (pinfunction "D0_1") (pintype "unspecified"))
      (node (ref "U53") (pin "8") (pinfunction "TX_8") (pintype "unspecified"))
    )
    (net (code "56") (name "R1") (class "Default")
      (node (ref "CN2") (pin "1") (pinfunction "R1_1") (pintype "input"))
      (node (ref "CN3") (pin "1") (pinfunction "R1_1") (pintype "input"))
      (node (ref "U25") (pin "3") (pinfunction "3_3") (pintype "unspecified"))
      (node (ref "U25") (pin "4") (pinfunction "4_4") (pintype "unspecified"))
      (node (ref "U26") (pin "3") (pinfunction "3_3") (pintype "unspecified"))
      (node (ref "U26") (pin "4") (pinfunction "4_4") (pintype "unspecified"))
      (node (ref "U27") (pin "3") (pinfunction "3_3") (pintype "unspecified"))
      (node (ref "U27") (pin "4") (pinfunction "4_4") (pintype "unspecified"))
      (node (ref "U37") (pin "6") (pinfunction "D5_6") (pintype "unspecified"))
      (node (ref "U38") (pin "3") (pinfunction "3_3") (pintype "unspecified"))
      (node (ref "U38") (pin "4") (pinfunction "4_4") (pintype "unspecified"))
      (node (ref "U39") (pin "3") (pinfunction "3_3") (pintype "unspecified"))
      (node (ref "U39") (pin "4") (pinfunction "4_4") (pintype "unspecified"))
      (node (ref "U40") (pin "3") (pinfunction "3_3") (pintype "unspecified"))
      (node (ref "U40") (pin "4") (pinfunction "4_4") (pintype "unspecified"))
      (node (ref "U47") (pin "6") (pinfunction "D5_6") (pintype "unspecified"))
    )
    (net (code "57") (name "R2") (class "Default")
      (node (ref "CN2") (pin "2") (pinfunction "R2_2") (pintype "input"))
      (node (ref "CN3") (pin "2") (pinfunction "R2_2") (pintype "input"))
      (node (ref "U22") (pin "3") (pinfunction "3_3") (pintype "unspecified"))
      (node (ref "U22") (pin "4") (pinfunction "4_4") (pintype "unspecified"))
      (node (ref "U23") (pin "3") (pinfunction "3_3") (pintype "unspecified"))
      (node (ref "U23") (pin "4") (pinfunction "4_4") (pintype "unspecified"))
      (node (ref "U24") (pin "3") (pinfunction "3_3") (pintype "unspecified"))
      (node (ref "U24") (pin "4") (pinfunction "4_4") (pintype "unspecified"))
      (node (ref "U37") (pin "7") (pinfunction "D6_7") (pintype "unspecified"))
      (node (ref "U41") (pin "3") (pinfunction "3_3") (pintype "unspecified"))
      (node (ref "U41") (pin "4") (pinfunction "4_4") (pintype "unspecified"))
      (node (ref "U42") (pin "3") (pinfunction "3_3") (pintype "unspecified"))
      (node (ref "U42") (pin "4") (pinfunction "4_4") (pintype "unspecified"))
      (node (ref "U43") (pin "3") (pinfunction "3_3") (pintype "unspecified"))
      (node (ref "U43") (pin "4") (pinfunction "4_4") (pintype "unspecified"))
      (node (ref "U47") (pin "7") (pinfunction "D6_7") (pintype "unspecified"))
    )
    (net (code "58") (name "R3") (class "Default")
      (node (ref "CN2") (pin "3") (pinfunction "R3_3") (pintype "input"))
      (node (ref "CN3") (pin "3") (pinfunction "R3_3") (pintype "input"))
      (node (ref "U19") (pin "3") (pinfunction "3_3") (pintype "unspecified"))
      (node (ref "U19") (pin "4") (pinfunction "4_4") (pintype "unspecified"))
      (node (ref "U20") (pin "3") (pinfunction "3_3") (pintype "unspecified"))
      (node (ref "U20") (pin "4") (pinfunction "4_4") (pintype "unspecified"))
      (node (ref "U21") (pin "3") (pinfunction "3_3") (pintype "unspecified"))
      (node (ref "U21") (pin "4") (pinfunction "4_4") (pintype "unspecified"))
      (node (ref "U37") (pin "8") (pinfunction "D7_8") (pintype "unspecified"))
      (node (ref "U44") (pin "3") (pinfunction "3_3") (pintype "unspecified"))
      (node (ref "U44") (pin "4") (pinfunction "4_4") (pintype "unspecified"))
      (node (ref "U45") (pin "3") (pinfunction "3_3") (pintype "unspecified"))
      (node (ref "U45") (pin "4") (pinfunction "4_4") (pintype "unspecified"))
      (node (ref "U46") (pin "3") (pinfunction "3_3") (pintype "unspecified"))
      (node (ref "U46") (pin "4") (pinfunction "4_4") (pintype "unspecified"))
      (node (ref "U47") (pin "8") (pinfunction "D7_8") (pintype "unspecified"))
    )
    (net (code "59") (name "RS") (class "Default")
      (node (ref "LCD2") (pin "4") (pinfunction "RS_4") (pintype "unspecified"))
      (node (ref "LCD3") (pin "4") (pinfunction "RS_4") (pintype "unspecified"))
      (node (ref "U35") (pin "RS") (pinfunction "6_RS") (pintype "unspecified"))
      (node (ref "U37") (pin "19") (pinfunction "A5_19") (pintype "unspecified"))
      (node (ref "U49") (pin "RS") (pinfunction "6_RS") (pintype "unspecified"))
      (node (ref "U51") (pin "19") (pinfunction "A5_19") (pintype "unspecified"))
    )
    (net (code "60") (name "VCC") (class "Default")
      (node (ref "C1") (pin "1") (pinfunction "1_1") (pintype "input"))
      (node (ref "C2") (pin "2") (pinfunction "2_2") (pintype "input"))
      (node (ref "C3") (pin "2") (pinfunction "2_2") (pintype "input"))
      (node (ref "C4") (pin "1") (pinfunction "1_1") (pintype "input"))
      (node (ref "C5") (pin "1") (pinfunction "1_1") (pintype "input"))
      (node (ref "C6") (pin "2") (pinfunction "2_2") (pintype "input"))
      (node (ref "D1") (pin "1") (pinfunction "K_1") (pintype "unspecified"))
      (node (ref "D2") (pin "1") (pinfunction "K_1") (pintype "unspecified"))
      (node (ref "D3") (pin "1") (pinfunction "K_1") (pintype "unspecified"))
      (node (ref "LCD2") (pin "15") (pinfunction "A_15") (pintype "unspecified"))
      (node (ref "LCD2") (pin "2") (pinfunction "Vdd_2") (pintype "unspecified"))
      (node (ref "LCD3") (pin "15") (pinfunction "A_15") (pintype "unspecified"))
      (node (ref "LCD3") (pin "2") (pinfunction "Vdd_2") (pintype "unspecified"))
      (node (ref "P1") (pin "1") (pinfunction "1_1") (pintype "input"))
      (node (ref "P2") (pin "1") (pinfunction "1_1") (pintype "input"))
      (node (ref "P3") (pin "1") (pinfunction "1_1") (pintype "input"))
      (node (ref "Q1") (pin "3") (pinfunction "E_3") (pintype "unspecified"))
      (node (ref "Q3") (pin "3") (pinfunction "E_3") (pintype "unspecified"))
      (node (ref "Q5") (pin "3") (pinfunction "E_3") (pintype "unspecified"))
      (node (ref "R1") (pin "2") (pinfunction "2_2") (pintype "unspecified"))
      (node (ref "R2") (pin "2") (pinfunction "2_2") (pintype "unspecified"))
      (node (ref "R5") (pin "2") (pinfunction "2_2") (pintype "unspecified"))
      (node (ref "R6") (pin "2") (pinfunction "2_2") (pintype "unspecified"))
      (node (ref "R7") (pin "2") (pinfunction "2_2") (pintype "unspecified"))
      (node (ref "R8") (pin "2") (pinfunction "2_2") (pintype "unspecified"))
      (node (ref "U10") (pin "1") (pinfunction "VCC_1") (pintype "unspecified"))
      (node (ref "U10") (pin "7") (pinfunction "SEL_7") (pintype "unspecified"))
      (node (ref "U11") (pin "2") (pinfunction "IN_2") (pintype "unspecified"))
      (node (ref "U15") (pin "1") (pinfunction "1_1") (pintype "unspecified"))
      (node (ref "U28") (pin "1") (pinfunction "VCC_1") (pintype "unspecified"))
      (node (ref "U28") (pin "7") (pinfunction "SEL_7") (pintype "unspecified"))
      (node (ref "U29") (pin "1") (pinfunction "1_1") (pintype "unspecified"))
      (node (ref "U33") (pin "2") (pinfunction "IN_2") (pintype "unspecified"))
      (node (ref "U34") (pin "VCC") (pinfunction "1_VCC") (pintype "unspecified"))
      (node (ref "U36") (pin "3") (pinfunction "2_3") (pintype "input"))
      (node (ref "U37") (pin "28") (pinfunction "5V_28") (pintype "passive"))
      (node (ref "U48") (pin "3") (pinfunction "2_3") (pintype "input"))
      (node (ref "U50") (pin "VCC") (pinfunction "1_VCC") (pintype "unspecified"))
      (node (ref "U51") (pin "28") (pinfunction "5V_28") (pintype "passive"))
      (node (ref "U52") (pin "28") (pinfunction "5V_28") (pintype "passive"))
      (node (ref "U53") (pin "1") (pinfunction "VCC_1") (pintype "unspecified"))
      (node (ref "U53") (pin "7") (pinfunction "SEL_7") (pintype "unspecified"))
      (node (ref "U54") (pin "28") (pinfunction "5V_28") (pintype "passive"))
      (node (ref "U55") (pin "2") (pinfunction "IN_2") (pintype "unspecified"))
      (node (ref "U58") (pin "1") (pinfunction "1_1") (pintype "unspecified"))
    )
    (net (code "61") (name "unconnected-(+-K-Pad2)") (class "Default")
      (node (ref "+") (pin "2") (pinfunction "K_2") (pintype "bidirectional"))
    )
    (net (code "62") (name "unconnected-(--K-Pad2)") (class "Default")
      (node (ref "-") (pin "2") (pinfunction "K_2") (pintype "bidirectional"))
    )
    (net (code "63") (name "unconnected-(LCD1-DB0-Pad7)") (class "Default")
      (node (ref "LCD1") (pin "7") (pinfunction "DB0_7") (pintype "unspecified"))
    )
    (net (code "64") (name "unconnected-(LCD1-DB1-Pad8)") (class "Default")
      (node (ref "LCD1") (pin "8") (pinfunction "DB1_8") (pintype "unspecified"))
    )
    (net (code "65") (name "unconnected-(LCD1-DB2-Pad9)") (class "Default")
      (node (ref "LCD1") (pin "9") (pinfunction "DB2_9") (pintype "unspecified"))
    )
    (net (code "66") (name "unconnected-(LCD1-DB3-Pad10)") (class "Default")
      (node (ref "LCD1") (pin "10") (pinfunction "DB3_10") (pintype "unspecified"))
    )
    (net (code "67") (name "unconnected-(LCD2-DB0-Pad7)") (class "Default")
      (node (ref "LCD2") (pin "7") (pinfunction "DB0_7") (pintype "unspecified"))
    )
    (net (code "68") (name "unconnected-(LCD2-DB1-Pad8)") (class "Default")
      (node (ref "LCD2") (pin "8") (pinfunction "DB1_8") (pintype "unspecified"))
    )
    (net (code "69") (name "unconnected-(LCD2-DB2-Pad9)") (class "Default")
      (node (ref "LCD2") (pin "9") (pinfunction "DB2_9") (pintype "unspecified"))
    )
    (net (code "70") (name "unconnected-(LCD2-DB3-Pad10)") (class "Default")
      (node (ref "LCD2") (pin "10") (pinfunction "DB3_10") (pintype "unspecified"))
    )
    (net (code "71") (name "unconnected-(LCD3-DB0-Pad7)") (class "Default")
      (node (ref "LCD3") (pin "7") (pinfunction "DB0_7") (pintype "unspecified"))
    )
    (net (code "72") (name "unconnected-(LCD3-DB1-Pad8)") (class "Default")
      (node (ref "LCD3") (pin "8") (pinfunction "DB1_8") (pintype "unspecified"))
    )
    (net (code "73") (name "unconnected-(LCD3-DB2-Pad9)") (class "Default")
      (node (ref "LCD3") (pin "9") (pinfunction "DB2_9") (pintype "unspecified"))
    )
    (net (code "74") (name "unconnected-(LCD3-DB3-Pad10)") (class "Default")
      (node (ref "LCD3") (pin "10") (pinfunction "DB3_10") (pintype "unspecified"))
    )
    (net (code "75") (name "unconnected-(U10-D1-Pad9)") (class "Default")
      (node (ref "U10") (pin "9") (pinfunction "D1_9") (pintype "unspecified"))
    )
    (net (code "76") (name "unconnected-(U10-D2-Pad10)") (class "Default")
      (node (ref "U10") (pin "10") (pinfunction "D2_10") (pintype "unspecified"))
    )
    (net (code "77") (name "unconnected-(U10-NC-Pad2)") (class "Default")
      (node (ref "U10") (pin "2") (pinfunction "NC_2") (pintype "unspecified"))
    )
    (net (code "78") (name "unconnected-(U10-NC-Pad5)") (class "Default")
      (node (ref "U10") (pin "5") (pinfunction "NC_5") (pintype "unspecified"))
    )
    (net (code "79") (name "unconnected-(U10-NC-Pad6)") (class "Default")
      (node (ref "U10") (pin "6") (pinfunction "NC_6") (pintype "unspecified"))
    )
    (net (code "80") (name "unconnected-(U11-NO-Pad5)") (class "Default")
      (node (ref "U11") (pin "5") (pinfunction "NO_5") (pintype "unspecified"))
    )
    (net (code "81") (name "unconnected-(U28-D1-Pad9)") (class "Default")
      (node (ref "U28") (pin "9") (pinfunction "D1_9") (pintype "unspecified"))
    )
    (net (code "82") (name "unconnected-(U28-D2-Pad10)") (class "Default")
      (node (ref "U28") (pin "10") (pinfunction "D2_10") (pintype "unspecified"))
    )
    (net (code "83") (name "unconnected-(U28-NC-Pad2)") (class "Default")
      (node (ref "U28") (pin "2") (pinfunction "NC_2") (pintype "unspecified"))
    )
    (net (code "84") (name "unconnected-(U28-NC-Pad5)") (class "Default")
      (node (ref "U28") (pin "5") (pinfunction "NC_5") (pintype "unspecified"))
    )
    (net (code "85") (name "unconnected-(U28-NC-Pad6)") (class "Default")
      (node (ref "U28") (pin "6") (pinfunction "NC_6") (pintype "unspecified"))
    )
    (net (code "86") (name "unconnected-(U33-NO-Pad5)") (class "Default")
      (node (ref "U33") (pin "5") (pinfunction "NO_5") (pintype "unspecified"))
    )
    (net (code "87") (name "unconnected-(U37-3V-Pad29)") (class "Default")
      (node (ref "U37") (pin "29") (pinfunction "3V_29") (pintype "passive"))
    )
    (net (code "88") (name "unconnected-(U37-AREF-Pad16)") (class "Default")
      (node (ref "U37") (pin "16") (pinfunction "AREF_16") (pintype "unspecified"))
    )
    (net (code "89") (name "unconnected-(U37-D1-Pad2)") (class "Default")
      (node (ref "U37") (pin "2") (pinfunction "D1_2") (pintype "unspecified"))
    )
    (net (code "90") (name "unconnected-(U37-D3-Pad4)") (class "Default")
      (node (ref "U37") (pin "4") (pinfunction "D3_4") (pintype "unspecified"))
    )
    (net (code "91") (name "unconnected-(U37-D4-Pad5)") (class "Default")
      (node (ref "U37") (pin "5") (pinfunction "D4_5") (pintype "unspecified"))
    )
    (net (code "92") (name "unconnected-(U37-D11-Pad12)") (class "Default")
      (node (ref "U37") (pin "12") (pinfunction "D11_12") (pintype "unspecified"))
    )
    (net (code "93") (name "unconnected-(U37-D12-Pad13)") (class "Default")
      (node (ref "U37") (pin "13") (pinfunction "D12_13") (pintype "unspecified"))
    )
    (net (code "94") (name "unconnected-(U37-D13-Pad14)") (class "Default")
      (node (ref "U37") (pin "14") (pinfunction "D13_14") (pintype "unspecified"))
    )
    (net (code "95") (name "unconnected-(U37-GND-Pad15)") (class "Default")
      (node (ref "U37") (pin "15") (pinfunction "GND_15") (pintype "passive"))
    )
    (net (code "96") (name "unconnected-(U37-GND2-Pad27)") (class "Default")
      (node (ref "U37") (pin "27") (pinfunction "GND2_27") (pintype "passive"))
    )
    (net (code "97") (name "unconnected-(U37-IOREF-Pad31)") (class "Default")
      (node (ref "U37") (pin "31") (pinfunction "IOREF_31") (pintype "unspecified"))
    )
    (net (code "98") (name "unconnected-(U37-RESET-Pad30)") (class "Default")
      (node (ref "U37") (pin "30") (pinfunction "RESET_30") (pintype "unspecified"))
    )
    (net (code "99") (name "unconnected-(U37-SCL-Pad18)") (class "Default")
      (node (ref "U37") (pin "18") (pinfunction "SCL_18") (pintype "unspecified"))
    )
    (net (code "100") (name "unconnected-(U37-SDA-Pad17)") (class "Default")
      (node (ref "U37") (pin "17") (pinfunction "SDA_17") (pintype "unspecified"))
    )
    (net (code "101") (name "unconnected-(U37-USART1-Pad32)") (class "Default")
      (node (ref "U37") (pin "32") (pinfunction "USART1_32") (pintype "unspecified"))
    )
    (net (code "102") (name "unconnected-(U47-3V-Pad29)") (class "Default")
      (node (ref "U47") (pin "29") (pinfunction "3V_29") (pintype "passive"))
    )
    (net (code "103") (name "unconnected-(U47-5V-Pad28)") (class "Default")
      (node (ref "U47") (pin "28") (pinfunction "5V_28") (pintype "passive"))
    )
    (net (code "104") (name "unconnected-(U47-A0-Pad24)") (class "Default")
      (node (ref "U47") (pin "24") (pinfunction "A0_24") (pintype "unspecified"))
    )
    (net (code "105") (name "unconnected-(U47-A1-Pad23)") (class "Default")
      (node (ref "U47") (pin "23") (pinfunction "A1_23") (pintype "unspecified"))
    )
    (net (code "106") (name "unconnected-(U47-A2-Pad22)") (class "Default")
      (node (ref "U47") (pin "22") (pinfunction "A2_22") (pintype "unspecified"))
    )
    (net (code "107") (name "unconnected-(U47-A3-Pad21)") (class "Default")
      (node (ref "U47") (pin "21") (pinfunction "A3_21") (pintype "unspecified"))
    )
    (net (code "108") (name "unconnected-(U47-A4-Pad20)") (class "Default")
      (node (ref "U47") (pin "20") (pinfunction "A4_20") (pintype "unspecified"))
    )
    (net (code "109") (name "unconnected-(U47-A5-Pad19)") (class "Default")
      (node (ref "U47") (pin "19") (pinfunction "A5_19") (pintype "unspecified"))
    )
    (net (code "110") (name "unconnected-(U47-AREF-Pad16)") (class "Default")
      (node (ref "U47") (pin "16") (pinfunction "AREF_16") (pintype "unspecified"))
    )
    (net (code "111") (name "unconnected-(U47-D0-Pad1)") (class "Default")
      (node (ref "U47") (pin "1") (pinfunction "D0_1") (pintype "unspecified"))
    )
    (net (code "112") (name "unconnected-(U47-D1-Pad2)") (class "Default")
      (node (ref "U47") (pin "2") (pinfunction "D1_2") (pintype "unspecified"))
    )
    (net (code "113") (name "unconnected-(U47-D2-Pad3)") (class "Default")
      (node (ref "U47") (pin "3") (pinfunction "D2_3") (pintype "unspecified"))
    )
    (net (code "114") (name "unconnected-(U47-D3-Pad4)") (class "Default")
      (node (ref "U47") (pin "4") (pinfunction "D3_4") (pintype "unspecified"))
    )
    (net (code "115") (name "unconnected-(U47-D4-Pad5)") (class "Default")
      (node (ref "U47") (pin "5") (pinfunction "D4_5") (pintype "unspecified"))
    )
    (net (code "116") (name "unconnected-(U47-D11-Pad12)") (class "Default")
      (node (ref "U47") (pin "12") (pinfunction "D11_12") (pintype "unspecified"))
    )
    (net (code "117") (name "unconnected-(U47-D12-Pad13)") (class "Default")
      (node (ref "U47") (pin "13") (pinfunction "D12_13") (pintype "unspecified"))
    )
    (net (code "118") (name "unconnected-(U47-D13-Pad14)") (class "Default")
      (node (ref "U47") (pin "14") (pinfunction "D13_14") (pintype "unspecified"))
    )
    (net (code "119") (name "unconnected-(U47-GND-Pad15)") (class "Default")
      (node (ref "U47") (pin "15") (pinfunction "GND_15") (pintype "passive"))
    )
    (net (code "120") (name "unconnected-(U47-GND1-Pad26)") (class "Default")
      (node (ref "U47") (pin "26") (pinfunction "GND1_26") (pintype "passive"))
    )
    (net (code "121") (name "unconnected-(U47-GND2-Pad27)") (class "Default")
      (node (ref "U47") (pin "27") (pinfunction "GND2_27") (pintype "passive"))
    )
    (net (code "122") (name "unconnected-(U47-IOREF-Pad31)") (class "Default")
      (node (ref "U47") (pin "31") (pinfunction "IOREF_31") (pintype "unspecified"))
    )
    (net (code "123") (name "unconnected-(U47-RESET-Pad30)") (class "Default")
      (node (ref "U47") (pin "30") (pinfunction "RESET_30") (pintype "unspecified"))
    )
    (net (code "124") (name "unconnected-(U47-SCL-Pad18)") (class "Default")
      (node (ref "U47") (pin "18") (pinfunction "SCL_18") (pintype "unspecified"))
    )
    (net (code "125") (name "unconnected-(U47-SDA-Pad17)") (class "Default")
      (node (ref "U47") (pin "17") (pinfunction "SDA_17") (pintype "unspecified"))
    )
    (net (code "126") (name "unconnected-(U47-USART1-Pad32)") (class "Default")
      (node (ref "U47") (pin "32") (pinfunction "USART1_32") (pintype "unspecified"))
    )
    (net (code "127") (name "unconnected-(U47-VIN-Pad25)") (class "Default")
      (node (ref "U47") (pin "25") (pinfunction "VIN_25") (pintype "passive"))
    )
    (net (code "128") (name "unconnected-(U51-3V-Pad29)") (class "Default")
      (node (ref "U51") (pin "29") (pinfunction "3V_29") (pintype "passive"))
    )
    (net (code "129") (name "unconnected-(U51-AREF-Pad16)") (class "Default")
      (node (ref "U51") (pin "16") (pinfunction "AREF_16") (pintype "unspecified"))
    )
    (net (code "130") (name "unconnected-(U51-D0-Pad1)") (class "Default")
      (node (ref "U51") (pin "1") (pinfunction "D0_1") (pintype "unspecified"))
    )
    (net (code "131") (name "unconnected-(U51-D1-Pad2)") (class "Default")
      (node (ref "U51") (pin "2") (pinfunction "D1_2") (pintype "unspecified"))
    )
    (net (code "132") (name "unconnected-(U51-D2-Pad3)") (class "Default")
      (node (ref "U51") (pin "3") (pinfunction "D2_3") (pintype "unspecified"))
    )
    (net (code "133") (name "unconnected-(U51-D3-Pad4)") (class "Default")
      (node (ref "U51") (pin "4") (pinfunction "D3_4") (pintype "unspecified"))
    )
    (net (code "134") (name "unconnected-(U51-D4-Pad5)") (class "Default")
      (node (ref "U51") (pin "5") (pinfunction "D4_5") (pintype "unspecified"))
    )
    (net (code "135") (name "unconnected-(U51-D5-Pad6)") (class "Default")
      (node (ref "U51") (pin "6") (pinfunction "D5_6") (pintype "unspecified"))
    )
    (net (code "136") (name "unconnected-(U51-D6-Pad7)") (class "Default")
      (node (ref "U51") (pin "7") (pinfunction "D6_7") (pintype "unspecified"))
    )
    (net (code "137") (name "unconnected-(U51-D7-Pad8)") (class "Default")
      (node (ref "U51") (pin "8") (pinfunction "D7_8") (pintype "unspecified"))
    )
    (net (code "138") (name "unconnected-(U51-D8-Pad9)") (class "Default")
      (node (ref "U51") (pin "9") (pinfunction "D8_9") (pintype "unspecified"))
    )
    (net (code "139") (name "unconnected-(U51-D9-Pad10)") (class "Default")
      (node (ref "U51") (pin "10") (pinfunction "D9_10") (pintype "unspecified"))
    )
    (net (code "140") (name "unconnected-(U51-D10-Pad11)") (class "Default")
      (node (ref "U51") (pin "11") (pinfunction "D10_11") (pintype "unspecified"))
    )
    (net (code "141") (name "unconnected-(U51-D11-Pad12)") (class "Default")
      (node (ref "U51") (pin "12") (pinfunction "D11_12") (pintype "unspecified"))
    )
    (net (code "142") (name "unconnected-(U51-D12-Pad13)") (class "Default")
      (node (ref "U51") (pin "13") (pinfunction "D12_13") (pintype "unspecified"))
    )
    (net (code "143") (name "unconnected-(U51-D13-Pad14)") (class "Default")
      (node (ref "U51") (pin "14") (pinfunction "D13_14") (pintype "unspecified"))
    )
    (net (code "144") (name "unconnected-(U51-GND-Pad15)") (class "Default")
      (node (ref "U51") (pin "15") (pinfunction "GND_15") (pintype "passive"))
    )
    (net (code "145") (name "unconnected-(U51-GND2-Pad27)") (class "Default")
      (node (ref "U51") (pin "27") (pinfunction "GND2_27") (pintype "passive"))
    )
    (net (code "146") (name "unconnected-(U51-IOREF-Pad31)") (class "Default")
      (node (ref "U51") (pin "31") (pinfunction "IOREF_31") (pintype "unspecified"))
    )
    (net (code "147") (name "unconnected-(U51-RESET-Pad30)") (class "Default")
      (node (ref "U51") (pin "30") (pinfunction "RESET_30") (pintype "unspecified"))
    )
    (net (code "148") (name "unconnected-(U51-SCL-Pad18)") (class "Default")
      (node (ref "U51") (pin "18") (pinfunction "SCL_18") (pintype "unspecified"))
    )
    (net (code "149") (name "unconnected-(U51-SDA-Pad17)") (class "Default")
      (node (ref "U51") (pin "17") (pinfunction "SDA_17") (pintype "unspecified"))
    )
    (net (code "150") (name "unconnected-(U51-USART1-Pad32)") (class "Default")
      (node (ref "U51") (pin "32") (pinfunction "USART1_32") (pintype "unspecified"))
    )
    (net (code "151") (name "unconnected-(U51-VIN-Pad25)") (class "Default")
      (node (ref "U51") (pin "25") (pinfunction "VIN_25") (pintype "passive"))
    )
    (net (code "152") (name "unconnected-(U52-3V-Pad29)") (class "Default")
      (node (ref "U52") (pin "29") (pinfunction "3V_29") (pintype "passive"))
    )
    (net (code "153") (name "unconnected-(U52-A0-Pad24)") (class "Default")
      (node (ref "U52") (pin "24") (pinfunction "A0_24") (pintype "unspecified"))
    )
    (net (code "154") (name "unconnected-(U52-A1-Pad23)") (class "Default")
      (node (ref "U52") (pin "23") (pinfunction "A1_23") (pintype "unspecified"))
    )
    (net (code "155") (name "unconnected-(U52-A2-Pad22)") (class "Default")
      (node (ref "U52") (pin "22") (pinfunction "A2_22") (pintype "unspecified"))
    )
    (net (code "156") (name "unconnected-(U52-A3-Pad21)") (class "Default")
      (node (ref "U52") (pin "21") (pinfunction "A3_21") (pintype "unspecified"))
    )
    (net (code "157") (name "unconnected-(U52-A4-Pad20)") (class "Default")
      (node (ref "U52") (pin "20") (pinfunction "A4_20") (pintype "unspecified"))
    )
    (net (code "158") (name "unconnected-(U52-A5-Pad19)") (class "Default")
      (node (ref "U52") (pin "19") (pinfunction "A5_19") (pintype "unspecified"))
    )
    (net (code "159") (name "unconnected-(U52-AREF-Pad16)") (class "Default")
      (node (ref "U52") (pin "16") (pinfunction "AREF_16") (pintype "unspecified"))
    )
    (net (code "160") (name "unconnected-(U52-D1-Pad2)") (class "Default")
      (node (ref "U52") (pin "2") (pinfunction "D1_2") (pintype "unspecified"))
    )
    (net (code "161") (name "unconnected-(U52-D2-Pad3)") (class "Default")
      (node (ref "U52") (pin "3") (pinfunction "D2_3") (pintype "unspecified"))
    )
    (net (code "162") (name "unconnected-(U52-D3-Pad4)") (class "Default")
      (node (ref "U52") (pin "4") (pinfunction "D3_4") (pintype "unspecified"))
    )
    (net (code "163") (name "unconnected-(U52-D4-Pad5)") (class "Default")
      (node (ref "U52") (pin "5") (pinfunction "D4_5") (pintype "unspecified"))
    )
    (net (code "164") (name "unconnected-(U52-D5-Pad6)") (class "Default")
      (node (ref "U52") (pin "6") (pinfunction "D5_6") (pintype "unspecified"))
    )
    (net (code "165") (name "unconnected-(U52-D6-Pad7)") (class "Default")
      (node (ref "U52") (pin "7") (pinfunction "D6_7") (pintype "unspecified"))
    )
    (net (code "166") (name "unconnected-(U52-D7-Pad8)") (class "Default")
      (node (ref "U52") (pin "8") (pinfunction "D7_8") (pintype "unspecified"))
    )
    (net (code "167") (name "unconnected-(U52-D8-Pad9)") (class "Default")
      (node (ref "U52") (pin "9") (pinfunction "D8_9") (pintype "unspecified"))
    )
    (net (code "168") (name "unconnected-(U52-D9-Pad10)") (class "Default")
      (node (ref "U52") (pin "10") (pinfunction "D9_10") (pintype "unspecified"))
    )
    (net (code "169") (name "unconnected-(U52-D10-Pad11)") (class "Default")
      (node (ref "U52") (pin "11") (pinfunction "D10_11") (pintype "unspecified"))
    )
    (net (code "170") (name "unconnected-(U52-D11-Pad12)") (class "Default")
      (node (ref "U52") (pin "12") (pinfunction "D11_12") (pintype "unspecified"))
    )
    (net (code "171") (name "unconnected-(U52-D12-Pad13)") (class "Default")
      (node (ref "U52") (pin "13") (pinfunction "D12_13") (pintype "unspecified"))
    )
    (net (code "172") (name "unconnected-(U52-D13-Pad14)") (class "Default")
      (node (ref "U52") (pin "14") (pinfunction "D13_14") (pintype "unspecified"))
    )
    (net (code "173") (name "unconnected-(U52-GND-Pad15)") (class "Default")
      (node (ref "U52") (pin "15") (pinfunction "GND_15") (pintype "passive"))
    )
    (net (code "174") (name "unconnected-(U52-GND2-Pad27)") (class "Default")
      (node (ref "U52") (pin "27") (pinfunction "GND2_27") (pintype "passive"))
    )
    (net (code "175") (name "unconnected-(U52-IOREF-Pad31)") (class "Default")
      (node (ref "U52") (pin "31") (pinfunction "IOREF_31") (pintype "unspecified"))
    )
    (net (code "176") (name "unconnected-(U52-RESET-Pad30)") (class "Default")
      (node (ref "U52") (pin "30") (pinfunction "RESET_30") (pintype "unspecified"))
    )
    (net (code "177") (name "unconnected-(U52-SCL-Pad18)") (class "Default")
      (node (ref "U52") (pin "18") (pinfunction "SCL_18") (pintype "unspecified"))
    )
    (net (code "178") (name "unconnected-(U52-SDA-Pad17)") (class "Default")
      (node (ref "U52") (pin "17") (pinfunction "SDA_17") (pintype "unspecified"))
    )
    (net (code "179") (name "unconnected-(U52-USART1-Pad32)") (class "Default")
      (node (ref "U52") (pin "32") (pinfunction "USART1_32") (pintype "unspecified"))
    )
    (net (code "180") (name "unconnected-(U52-VIN-Pad25)") (class "Default")
      (node (ref "U52") (pin "25") (pinfunction "VIN_25") (pintype "passive"))
    )
    (net (code "181") (name "unconnected-(U53-D1-Pad9)") (class "Default")
      (node (ref "U53") (pin "9") (pinfunction "D1_9") (pintype "unspecified"))
    )
    (net (code "182") (name "unconnected-(U53-D2-Pad10)") (class "Default")
      (node (ref "U53") (pin "10") (pinfunction "D2_10") (pintype "unspecified"))
    )
    (net (code "183") (name "unconnected-(U53-NC-Pad2)") (class "Default")
      (node (ref "U53") (pin "2") (pinfunction "NC_2") (pintype "unspecified"))
    )
    (net (code "184") (name "unconnected-(U53-NC-Pad5)") (class "Default")
      (node (ref "U53") (pin "5") (pinfunction "NC_5") (pintype "unspecified"))
    )
    (net (code "185") (name "unconnected-(U53-NC-Pad6)") (class "Default")
      (node (ref "U53") (pin "6") (pinfunction "NC_6") (pintype "unspecified"))
    )
    (net (code "186") (name "unconnected-(U54-3V-Pad29)") (class "Default")
      (node (ref "U54") (pin "29") (pinfunction "3V_29") (pintype "passive"))
    )
    (net (code "187") (name "unconnected-(U54-A0-Pad24)") (class "Default")
      (node (ref "U54") (pin "24") (pinfunction "A0_24") (pintype "unspecified"))
    )
    (net (code "188") (name "unconnected-(U54-A1-Pad23)") (class "Default")
      (node (ref "U54") (pin "23") (pinfunction "A1_23") (pintype "unspecified"))
    )
    (net (code "189") (name "unconnected-(U54-A2-Pad22)") (class "Default")
      (node (ref "U54") (pin "22") (pinfunction "A2_22") (pintype "unspecified"))
    )
    (net (code "190") (name "unconnected-(U54-A3-Pad21)") (class "Default")
      (node (ref "U54") (pin "21") (pinfunction "A3_21") (pintype "unspecified"))
    )
    (net (code "191") (name "unconnected-(U54-A4-Pad20)") (class "Default")
      (node (ref "U54") (pin "20") (pinfunction "A4_20") (pintype "unspecified"))
    )
    (net (code "192") (name "unconnected-(U54-A5-Pad19)") (class "Default")
      (node (ref "U54") (pin "19") (pinfunction "A5_19") (pintype "unspecified"))
    )
    (net (code "193") (name "unconnected-(U54-AREF-Pad16)") (class "Default")
      (node (ref "U54") (pin "16") (pinfunction "AREF_16") (pintype "unspecified"))
    )
    (net (code "194") (name "unconnected-(U54-D0-Pad1)") (class "Default")
      (node (ref "U54") (pin "1") (pinfunction "D0_1") (pintype "unspecified"))
    )
    (net (code "195") (name "unconnected-(U54-D1-Pad2)") (class "Default")
      (node (ref "U54") (pin "2") (pinfunction "D1_2") (pintype "unspecified"))
    )
    (net (code "196") (name "unconnected-(U54-D3-Pad4)") (class "Default")
      (node (ref "U54") (pin "4") (pinfunction "D3_4") (pintype "unspecified"))
    )
    (net (code "197") (name "unconnected-(U54-D4-Pad5)") (class "Default")
      (node (ref "U54") (pin "5") (pinfunction "D4_5") (pintype "unspecified"))
    )
    (net (code "198") (name "unconnected-(U54-D5-Pad6)") (class "Default")
      (node (ref "U54") (pin "6") (pinfunction "D5_6") (pintype "unspecified"))
    )
    (net (code "199") (name "unconnected-(U54-D6-Pad7)") (class "Default")
      (node (ref "U54") (pin "7") (pinfunction "D6_7") (pintype "unspecified"))
    )
    (net (code "200") (name "unconnected-(U54-D7-Pad8)") (class "Default")
      (node (ref "U54") (pin "8") (pinfunction "D7_8") (pintype "unspecified"))
    )
    (net (code "201") (name "unconnected-(U54-D8-Pad9)") (class "Default")
      (node (ref "U54") (pin "9") (pinfunction "D8_9") (pintype "unspecified"))
    )
    (net (code "202") (name "unconnected-(U54-D9-Pad10)") (class "Default")
      (node (ref "U54") (pin "10") (pinfunction "D9_10") (pintype "unspecified"))
    )
    (net (code "203") (name "unconnected-(U54-D10-Pad11)") (class "Default")
      (node (ref "U54") (pin "11") (pinfunction "D10_11") (pintype "unspecified"))
    )
    (net (code "204") (name "unconnected-(U54-D11-Pad12)") (class "Default")
      (node (ref "U54") (pin "12") (pinfunction "D11_12") (pintype "unspecified"))
    )
    (net (code "205") (name "unconnected-(U54-D12-Pad13)") (class "Default")
      (node (ref "U54") (pin "13") (pinfunction "D12_13") (pintype "unspecified"))
    )
    (net (code "206") (name "unconnected-(U54-D13-Pad14)") (class "Default")
      (node (ref "U54") (pin "14") (pinfunction "D13_14") (pintype "unspecified"))
    )
    (net (code "207") (name "unconnected-(U54-GND-Pad15)") (class "Default")
      (node (ref "U54") (pin "15") (pinfunction "GND_15") (pintype "passive"))
    )
    (net (code "208") (name "unconnected-(U54-GND2-Pad27)") (class "Default")
      (node (ref "U54") (pin "27") (pinfunction "GND2_27") (pintype "passive"))
    )
    (net (code "209") (name "unconnected-(U54-IOREF-Pad31)") (class "Default")
      (node (ref "U54") (pin "31") (pinfunction "IOREF_31") (pintype "unspecified"))
    )
    (net (code "210") (name "unconnected-(U54-RESET-Pad30)") (class "Default")
      (node (ref "U54") (pin "30") (pinfunction "RESET_30") (pintype "unspecified"))
    )
    (net (code "211") (name "unconnected-(U54-SCL-Pad18)") (class "Default")
      (node (ref "U54") (pin "18") (pinfunction "SCL_18") (pintype "unspecified"))
    )
    (net (code "212") (name "unconnected-(U54-SDA-Pad17)") (class "Default")
      (node (ref "U54") (pin "17") (pinfunction "SDA_17") (pintype "unspecified"))
    )
    (net (code "213") (name "unconnected-(U54-USART1-Pad32)") (class "Default")
      (node (ref "U54") (pin "32") (pinfunction "USART1_32") (pintype "unspecified"))
    )
    (net (code "214") (name "unconnected-(U55-NO-Pad5)") (class "Default")
      (node (ref "U55") (pin "5") (pinfunction "NO_5") (pintype "unspecified"))
    )
  )
)
